# Main_board_schematic.net
KiCad netlist of a schematic drawn in EAGLE
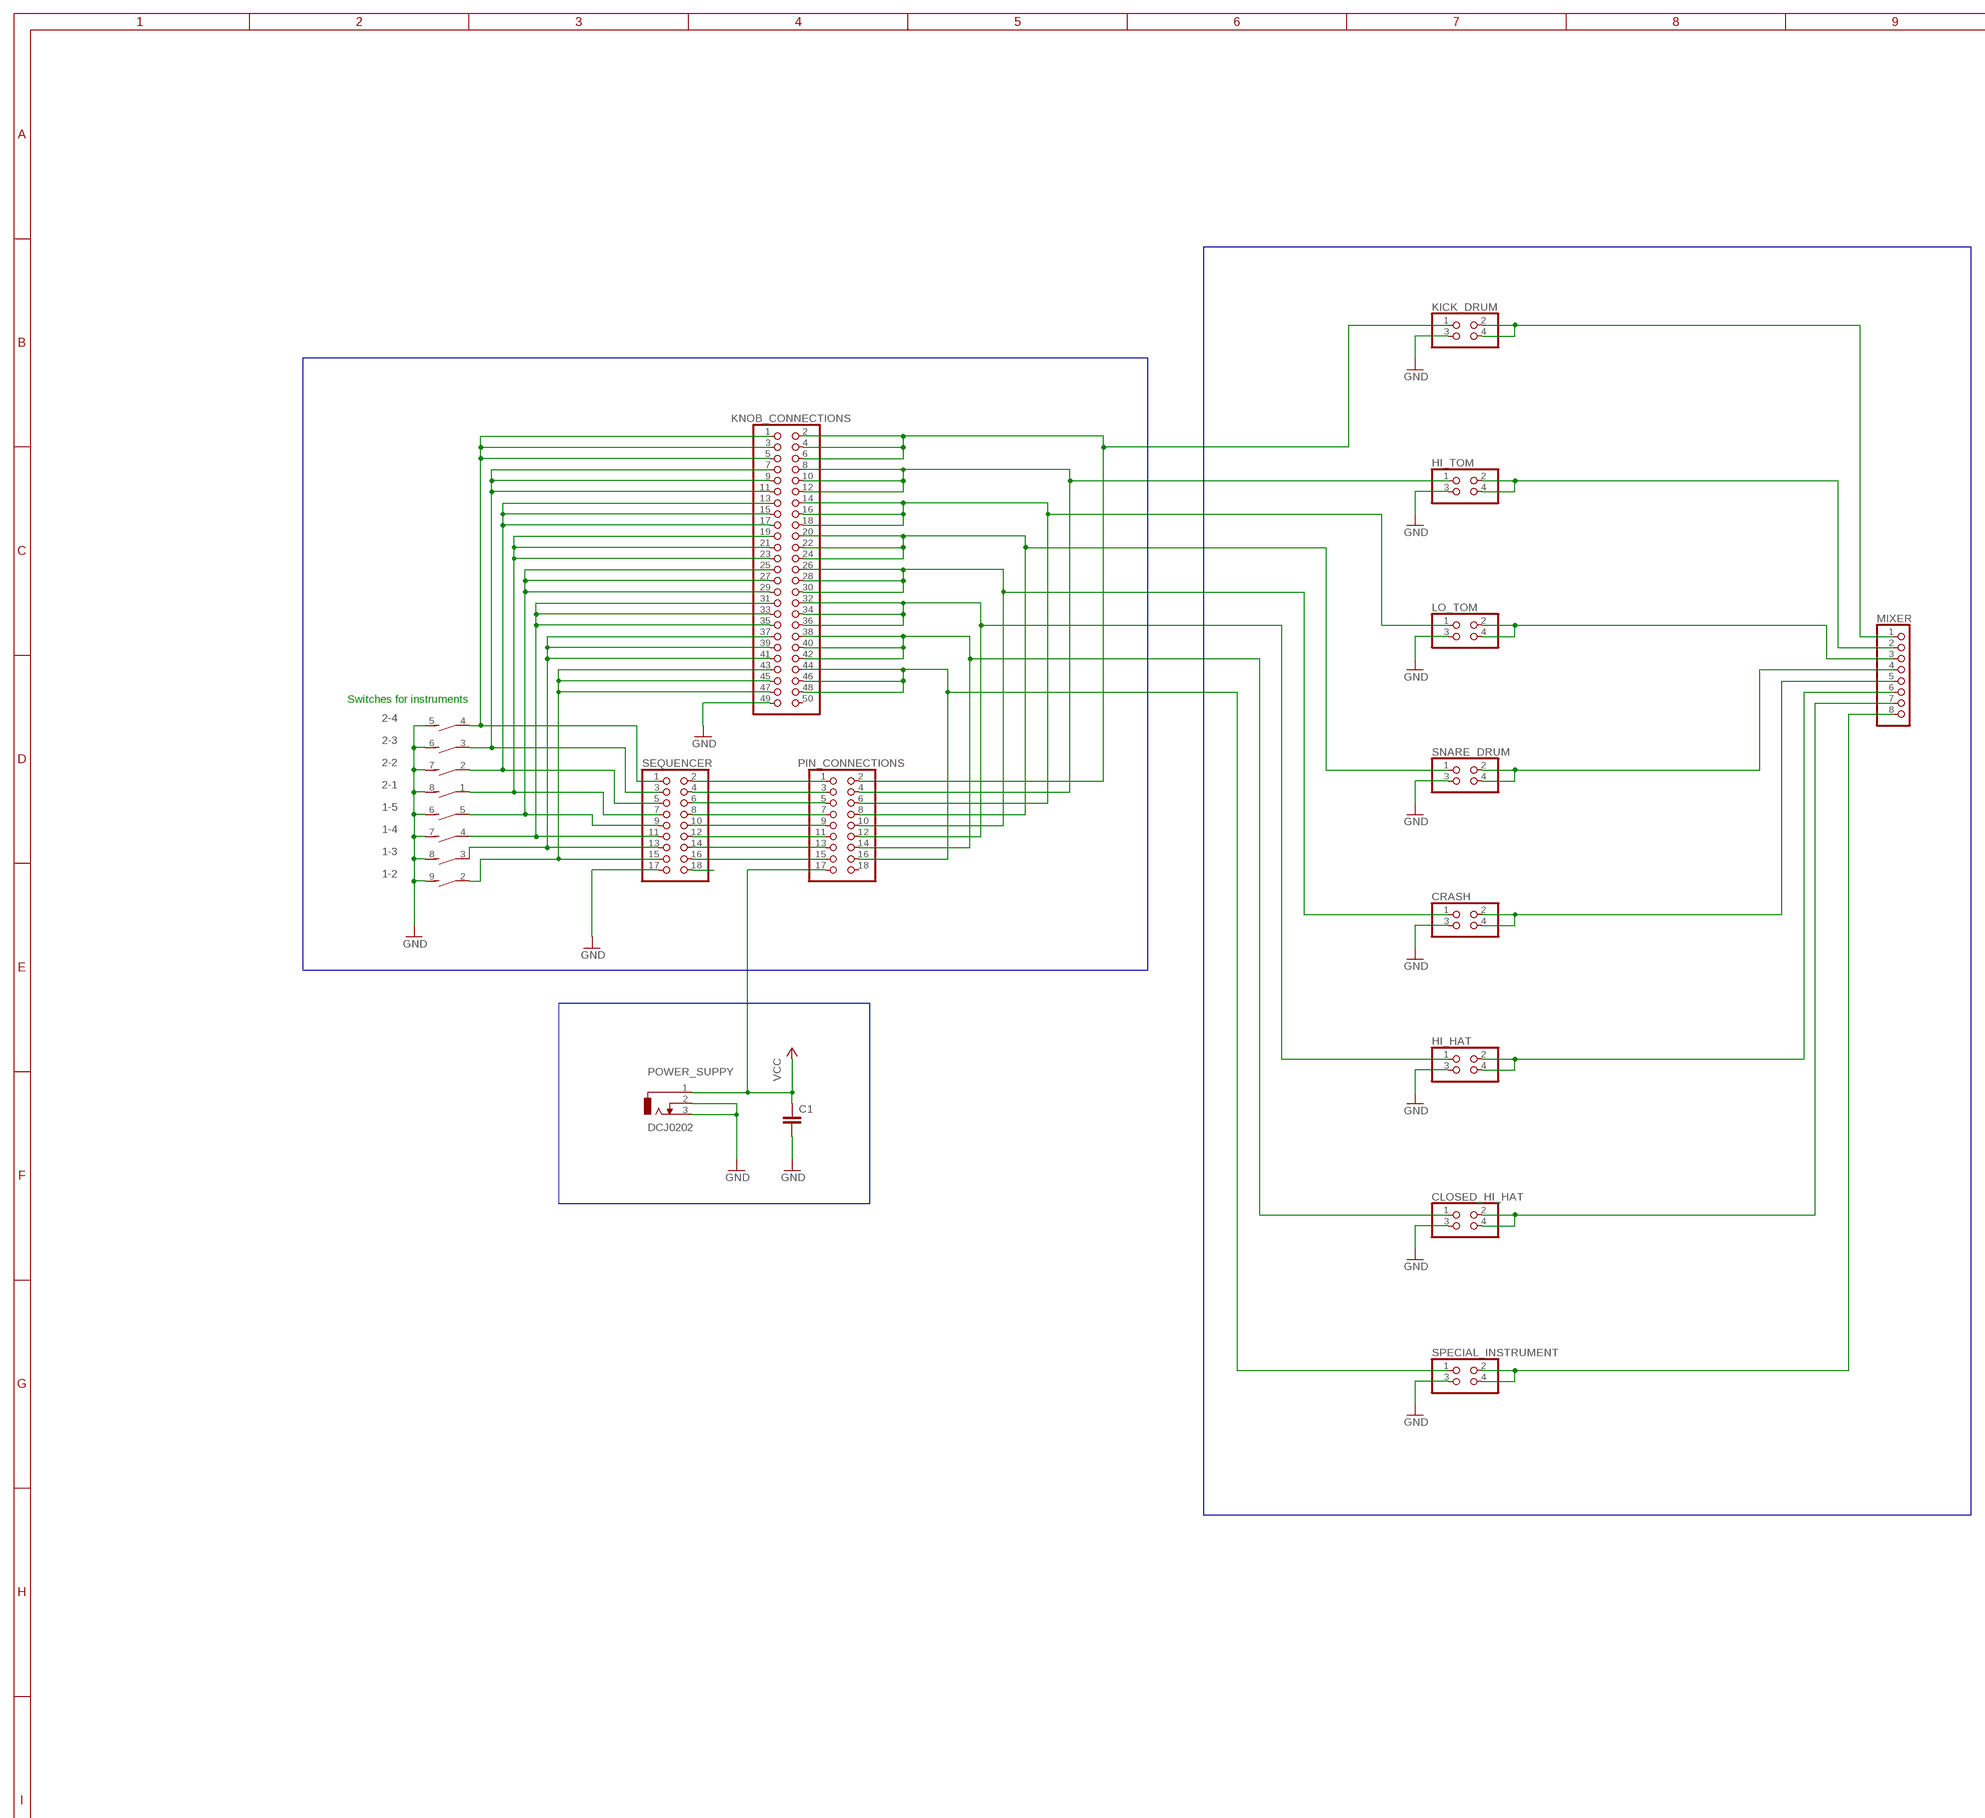
[diagram p0: schematic, sheet 1, part 1 of 2]
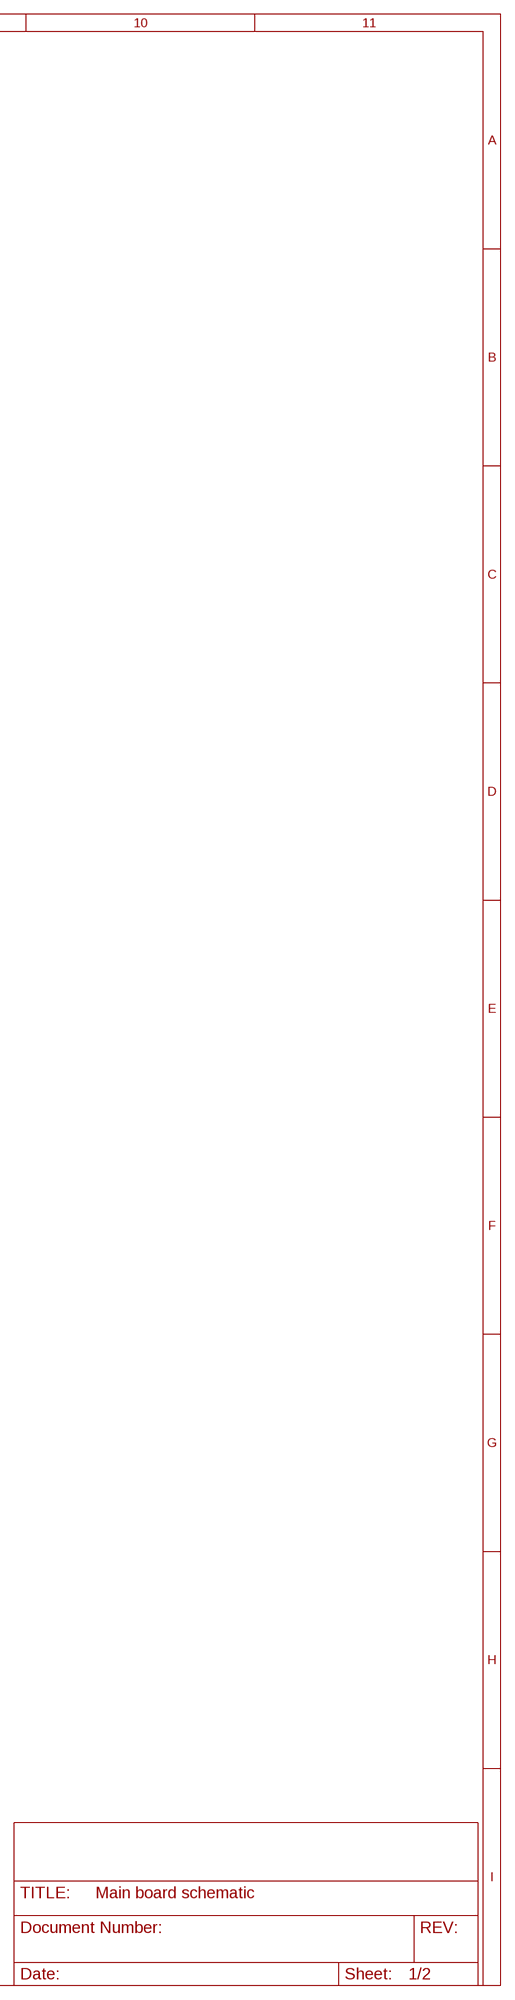
[diagram p1: schematic, sheet 1, part 2 of 2]
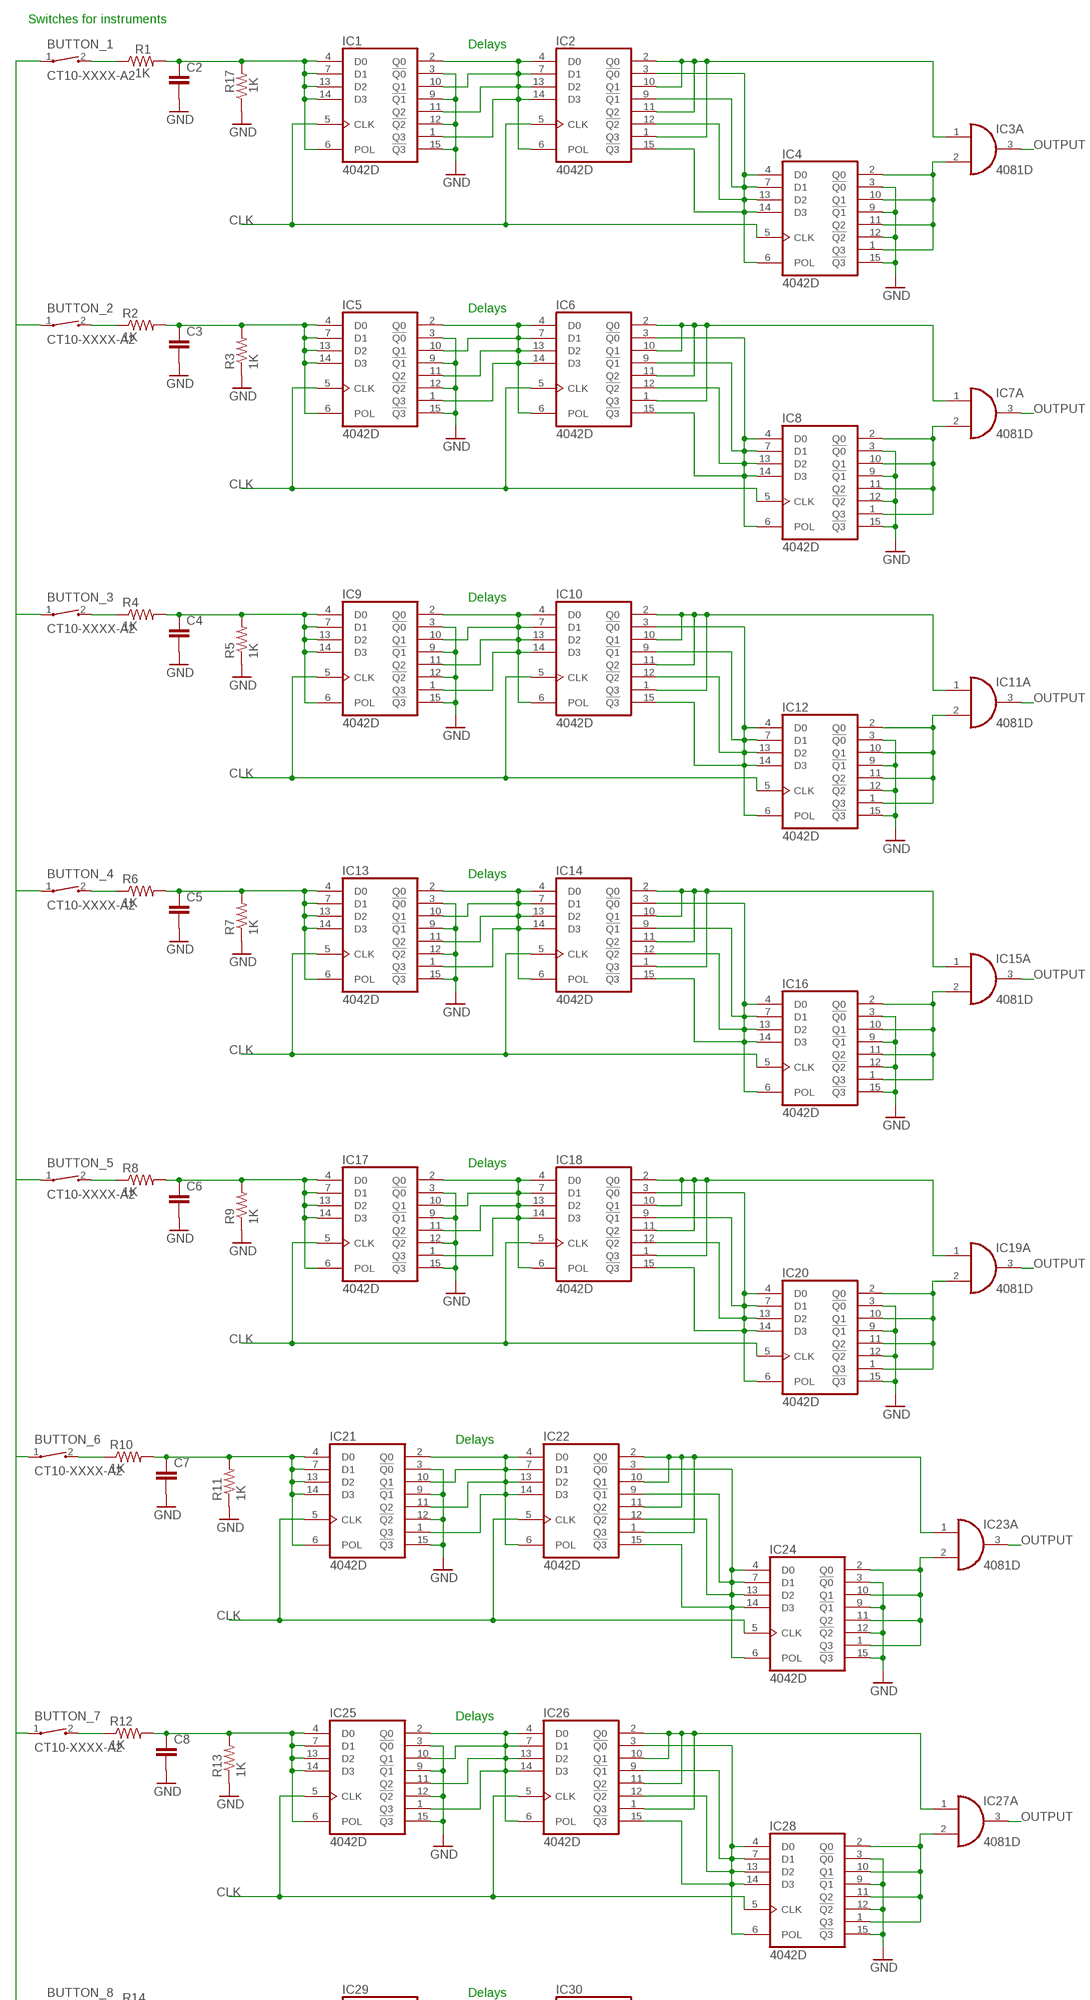
[diagram p2: schematic, sheet 2, part 1 of 3]
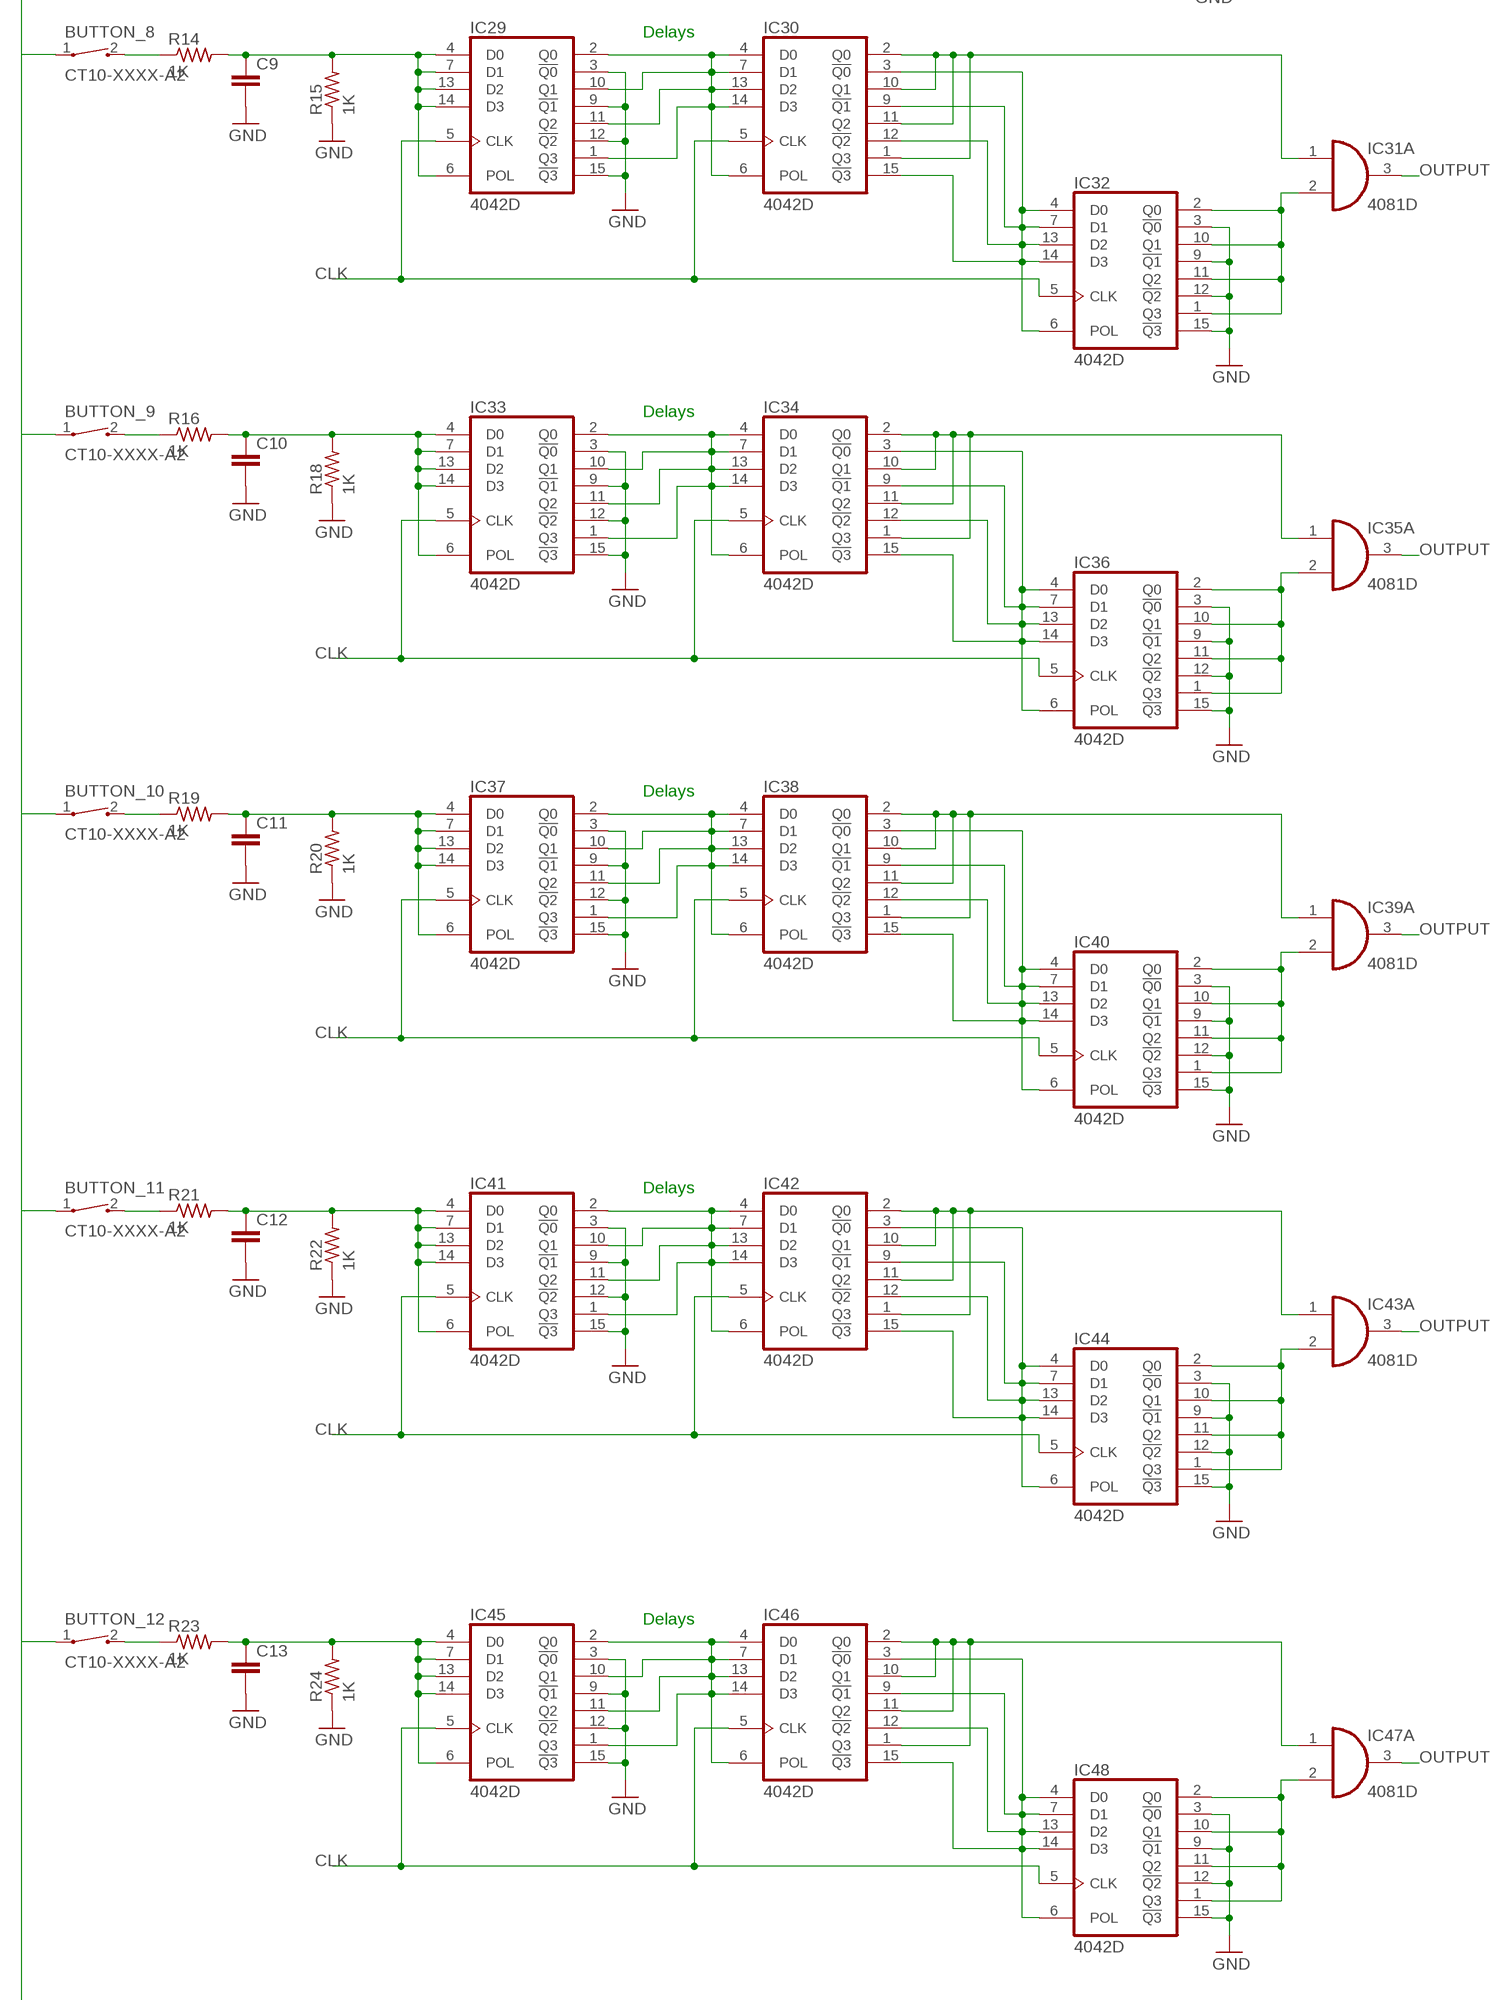
[diagram p3: schematic, sheet 2, part 2 of 3]
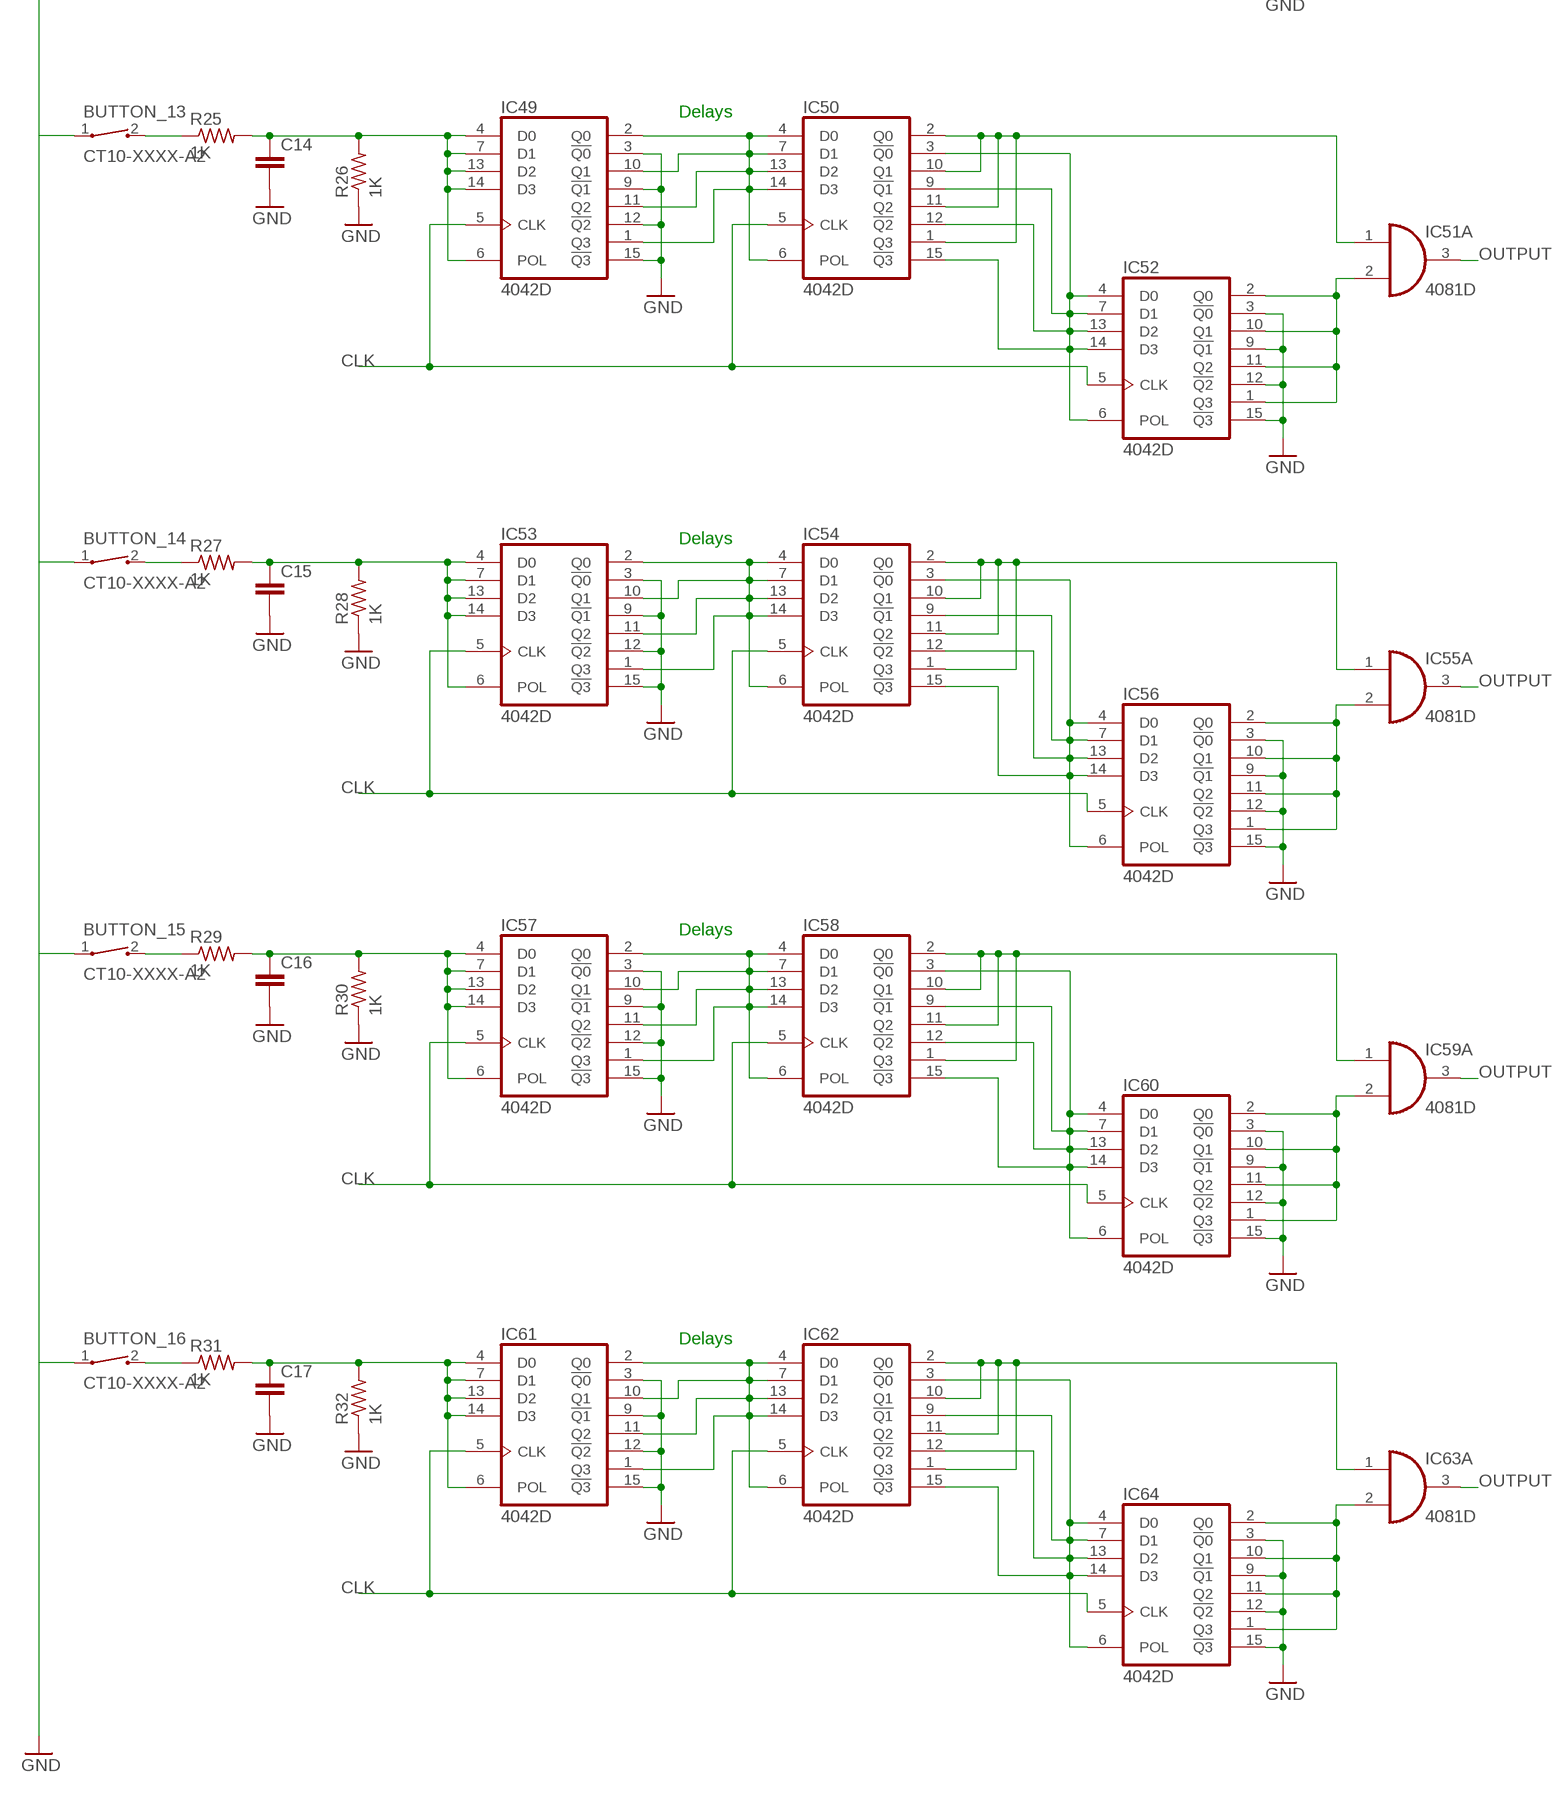
[diagram p4: schematic, sheet 2, part 3 of 3]

(export (version "E")
  (design (tool "Eeschema 10.0.6"))
  (components
    (comp (ref "BUTTON_1")
      (value "CT10-XXXX-A2")
      (footprint "eagle-import:CT10-XXXX-A2")
      (libsource (lib "eagle-import") (part "CT10-XXXX-A2"))
    )
    (comp (ref "BUTTON_2")
      (value "CT10-XXXX-A2")
      (footprint "eagle-import:CT10-XXXX-A2")
      (libsource (lib "eagle-import") (part "CT10-XXXX-A2"))
    )
    (comp (ref "BUTTON_3")
      (value "CT10-XXXX-A2")
      (footprint "eagle-import:CT10-XXXX-A2")
      (libsource (lib "eagle-import") (part "CT10-XXXX-A2"))
    )
    (comp (ref "BUTTON_4")
      (value "CT10-XXXX-A2")
      (footprint "eagle-import:CT10-XXXX-A2")
      (libsource (lib "eagle-import") (part "CT10-XXXX-A2"))
    )
    (comp (ref "BUTTON_5")
      (value "CT10-XXXX-A2")
      (footprint "eagle-import:CT10-XXXX-A2")
      (libsource (lib "eagle-import") (part "CT10-XXXX-A2"))
    )
    (comp (ref "BUTTON_6")
      (value "CT10-XXXX-A2")
      (footprint "eagle-import:CT10-XXXX-A2")
      (libsource (lib "eagle-import") (part "CT10-XXXX-A2"))
    )
    (comp (ref "BUTTON_7")
      (value "CT10-XXXX-A2")
      (footprint "eagle-import:CT10-XXXX-A2")
      (libsource (lib "eagle-import") (part "CT10-XXXX-A2"))
    )
    (comp (ref "BUTTON_8")
      (value "CT10-XXXX-A2")
      (footprint "eagle-import:CT10-XXXX-A2")
      (libsource (lib "eagle-import") (part "CT10-XXXX-A2"))
    )
    (comp (ref "BUTTON_9")
      (value "CT10-XXXX-A2")
      (footprint "eagle-import:CT10-XXXX-A2")
      (libsource (lib "eagle-import") (part "CT10-XXXX-A2"))
    )
    (comp (ref "BUTTON_10")
      (value "CT10-XXXX-A2")
      (footprint "eagle-import:CT10-XXXX-A2")
      (libsource (lib "eagle-import") (part "CT10-XXXX-A2"))
    )
    (comp (ref "BUTTON_11")
      (value "CT10-XXXX-A2")
      (footprint "eagle-import:CT10-XXXX-A2")
      (libsource (lib "eagle-import") (part "CT10-XXXX-A2"))
    )
    (comp (ref "BUTTON_12")
      (value "CT10-XXXX-A2")
      (footprint "eagle-import:CT10-XXXX-A2")
      (libsource (lib "eagle-import") (part "CT10-XXXX-A2"))
    )
    (comp (ref "BUTTON_13")
      (value "CT10-XXXX-A2")
      (footprint "eagle-import:CT10-XXXX-A2")
      (libsource (lib "eagle-import") (part "CT10-XXXX-A2"))
    )
    (comp (ref "BUTTON_14")
      (value "CT10-XXXX-A2")
      (footprint "eagle-import:CT10-XXXX-A2")
      (libsource (lib "eagle-import") (part "CT10-XXXX-A2"))
    )
    (comp (ref "BUTTON_15")
      (value "CT10-XXXX-A2")
      (footprint "eagle-import:CT10-XXXX-A2")
      (libsource (lib "eagle-import") (part "CT10-XXXX-A2"))
    )
    (comp (ref "BUTTON_16")
      (value "CT10-XXXX-A2")
      (footprint "eagle-import:CT10-XXXX-A2")
      (libsource (lib "eagle-import") (part "CT10-XXXX-A2"))
    )
    (comp (ref "C2")
      (value "C5/3")
      (footprint "eagle-import:C5B3")
      (libsource (lib "eagle-import") (part "C5/3"))
    )
    (comp (ref "C3")
      (value "C5/3")
      (footprint "eagle-import:C5B3")
      (libsource (lib "eagle-import") (part "C5/3"))
    )
    (comp (ref "C4")
      (value "C5/3")
      (footprint "eagle-import:C5B3")
      (libsource (lib "eagle-import") (part "C5/3"))
    )
    (comp (ref "C5")
      (value "C5/3")
      (footprint "eagle-import:C5B3")
      (libsource (lib "eagle-import") (part "C5/3"))
    )
    (comp (ref "C6")
      (value "C5/3")
      (footprint "eagle-import:C5B3")
      (libsource (lib "eagle-import") (part "C5/3"))
    )
    (comp (ref "C7")
      (value "C5/3")
      (footprint "eagle-import:C5B3")
      (libsource (lib "eagle-import") (part "C5/3"))
    )
    (comp (ref "C8")
      (value "C5/3")
      (footprint "eagle-import:C5B3")
      (libsource (lib "eagle-import") (part "C5/3"))
    )
    (comp (ref "C9")
      (value "C5/3")
      (footprint "eagle-import:C5B3")
      (libsource (lib "eagle-import") (part "C5/3"))
    )
    (comp (ref "C10")
      (value "C5/3")
      (footprint "eagle-import:C5B3")
      (libsource (lib "eagle-import") (part "C5/3"))
    )
    (comp (ref "C11")
      (value "C5/3")
      (footprint "eagle-import:C5B3")
      (libsource (lib "eagle-import") (part "C5/3"))
    )
    (comp (ref "C12")
      (value "C5/3")
      (footprint "eagle-import:C5B3")
      (libsource (lib "eagle-import") (part "C5/3"))
    )
    (comp (ref "C13")
      (value "C5/3")
      (footprint "eagle-import:C5B3")
      (libsource (lib "eagle-import") (part "C5/3"))
    )
    (comp (ref "C14")
      (value "C5/3")
      (footprint "eagle-import:C5B3")
      (libsource (lib "eagle-import") (part "C5/3"))
    )
    (comp (ref "C15")
      (value "C5/3")
      (footprint "eagle-import:C5B3")
      (libsource (lib "eagle-import") (part "C5/3"))
    )
    (comp (ref "C16")
      (value "C5/3")
      (footprint "eagle-import:C5B3")
      (libsource (lib "eagle-import") (part "C5/3"))
    )
    (comp (ref "C17")
      (value "C5/3")
      (footprint "eagle-import:C5B3")
      (libsource (lib "eagle-import") (part "C5/3"))
    )
    (comp (ref "IC1")
      (value "4042D")
      (footprint "eagle-import:SO16")
      (libsource (lib "eagle-import") (part "4042D"))
    )
    (comp (ref "IC2")
      (value "4042D")
      (footprint "eagle-import:SO16")
      (libsource (lib "eagle-import") (part "4042D"))
    )
    (comp (ref "IC3")
      (value "4081D")
      (footprint "eagle-import:SO14")
      (libsource (lib "eagle-import") (part "4081D"))
    )
    (comp (ref "IC4")
      (value "4042D")
      (footprint "eagle-import:SO16")
      (libsource (lib "eagle-import") (part "4042D"))
    )
    (comp (ref "IC5")
      (value "4042D")
      (footprint "eagle-import:SO16")
      (libsource (lib "eagle-import") (part "4042D"))
    )
    (comp (ref "IC6")
      (value "4042D")
      (footprint "eagle-import:SO16")
      (libsource (lib "eagle-import") (part "4042D"))
    )
    (comp (ref "IC7")
      (value "4081D")
      (footprint "eagle-import:SO14")
      (libsource (lib "eagle-import") (part "4081D"))
    )
    (comp (ref "IC8")
      (value "4042D")
      (footprint "eagle-import:SO16")
      (libsource (lib "eagle-import") (part "4042D"))
    )
    (comp (ref "IC9")
      (value "4042D")
      (footprint "eagle-import:SO16")
      (libsource (lib "eagle-import") (part "4042D"))
    )
    (comp (ref "IC10")
      (value "4042D")
      (footprint "eagle-import:SO16")
      (libsource (lib "eagle-import") (part "4042D"))
    )
    (comp (ref "IC11")
      (value "4081D")
      (footprint "eagle-import:SO14")
      (libsource (lib "eagle-import") (part "4081D"))
    )
    (comp (ref "IC12")
      (value "4042D")
      (footprint "eagle-import:SO16")
      (libsource (lib "eagle-import") (part "4042D"))
    )
    (comp (ref "IC13")
      (value "4042D")
      (footprint "eagle-import:SO16")
      (libsource (lib "eagle-import") (part "4042D"))
    )
    (comp (ref "IC14")
      (value "4042D")
      (footprint "eagle-import:SO16")
      (libsource (lib "eagle-import") (part "4042D"))
    )
    (comp (ref "IC15")
      (value "4081D")
      (footprint "eagle-import:SO14")
      (libsource (lib "eagle-import") (part "4081D"))
    )
    (comp (ref "IC16")
      (value "4042D")
      (footprint "eagle-import:SO16")
      (libsource (lib "eagle-import") (part "4042D"))
    )
    (comp (ref "IC17")
      (value "4042D")
      (footprint "eagle-import:SO16")
      (libsource (lib "eagle-import") (part "4042D"))
    )
    (comp (ref "IC18")
      (value "4042D")
      (footprint "eagle-import:SO16")
      (libsource (lib "eagle-import") (part "4042D"))
    )
    (comp (ref "IC19")
      (value "4081D")
      (footprint "eagle-import:SO14")
      (libsource (lib "eagle-import") (part "4081D"))
    )
    (comp (ref "IC20")
      (value "4042D")
      (footprint "eagle-import:SO16")
      (libsource (lib "eagle-import") (part "4042D"))
    )
    (comp (ref "IC21")
      (value "4042D")
      (footprint "eagle-import:SO16")
      (libsource (lib "eagle-import") (part "4042D"))
    )
    (comp (ref "IC22")
      (value "4042D")
      (footprint "eagle-import:SO16")
      (libsource (lib "eagle-import") (part "4042D"))
    )
    (comp (ref "IC23")
      (value "4081D")
      (footprint "eagle-import:SO14")
      (libsource (lib "eagle-import") (part "4081D"))
    )
    (comp (ref "IC24")
      (value "4042D")
      (footprint "eagle-import:SO16")
      (libsource (lib "eagle-import") (part "4042D"))
    )
    (comp (ref "IC25")
      (value "4042D")
      (footprint "eagle-import:SO16")
      (libsource (lib "eagle-import") (part "4042D"))
    )
    (comp (ref "IC26")
      (value "4042D")
      (footprint "eagle-import:SO16")
      (libsource (lib "eagle-import") (part "4042D"))
    )
    (comp (ref "IC27")
      (value "4081D")
      (footprint "eagle-import:SO14")
      (libsource (lib "eagle-import") (part "4081D"))
    )
    (comp (ref "IC28")
      (value "4042D")
      (footprint "eagle-import:SO16")
      (libsource (lib "eagle-import") (part "4042D"))
    )
    (comp (ref "IC29")
      (value "4042D")
      (footprint "eagle-import:SO16")
      (libsource (lib "eagle-import") (part "4042D"))
    )
    (comp (ref "IC30")
      (value "4042D")
      (footprint "eagle-import:SO16")
      (libsource (lib "eagle-import") (part "4042D"))
    )
    (comp (ref "IC31")
      (value "4081D")
      (footprint "eagle-import:SO14")
      (libsource (lib "eagle-import") (part "4081D"))
    )
    (comp (ref "IC32")
      (value "4042D")
      (footprint "eagle-import:SO16")
      (libsource (lib "eagle-import") (part "4042D"))
    )
    (comp (ref "IC33")
      (value "4042D")
      (footprint "eagle-import:SO16")
      (libsource (lib "eagle-import") (part "4042D"))
    )
    (comp (ref "IC34")
      (value "4042D")
      (footprint "eagle-import:SO16")
      (libsource (lib "eagle-import") (part "4042D"))
    )
    (comp (ref "IC35")
      (value "4081D")
      (footprint "eagle-import:SO14")
      (libsource (lib "eagle-import") (part "4081D"))
    )
    (comp (ref "IC36")
      (value "4042D")
      (footprint "eagle-import:SO16")
      (libsource (lib "eagle-import") (part "4042D"))
    )
    (comp (ref "IC37")
      (value "4042D")
      (footprint "eagle-import:SO16")
      (libsource (lib "eagle-import") (part "4042D"))
    )
    (comp (ref "IC38")
      (value "4042D")
      (footprint "eagle-import:SO16")
      (libsource (lib "eagle-import") (part "4042D"))
    )
    (comp (ref "IC39")
      (value "4081D")
      (footprint "eagle-import:SO14")
      (libsource (lib "eagle-import") (part "4081D"))
    )
    (comp (ref "IC40")
      (value "4042D")
      (footprint "eagle-import:SO16")
      (libsource (lib "eagle-import") (part "4042D"))
    )
    (comp (ref "IC41")
      (value "4042D")
      (footprint "eagle-import:SO16")
      (libsource (lib "eagle-import") (part "4042D"))
    )
    (comp (ref "IC42")
      (value "4042D")
      (footprint "eagle-import:SO16")
      (libsource (lib "eagle-import") (part "4042D"))
    )
    (comp (ref "IC43")
      (value "4081D")
      (footprint "eagle-import:SO14")
      (libsource (lib "eagle-import") (part "4081D"))
    )
    (comp (ref "IC44")
      (value "4042D")
      (footprint "eagle-import:SO16")
      (libsource (lib "eagle-import") (part "4042D"))
    )
    (comp (ref "IC45")
      (value "4042D")
      (footprint "eagle-import:SO16")
      (libsource (lib "eagle-import") (part "4042D"))
    )
    (comp (ref "IC46")
      (value "4042D")
      (footprint "eagle-import:SO16")
      (libsource (lib "eagle-import") (part "4042D"))
    )
    (comp (ref "IC47")
      (value "4081D")
      (footprint "eagle-import:SO14")
      (libsource (lib "eagle-import") (part "4081D"))
    )
    (comp (ref "IC48")
      (value "4042D")
      (footprint "eagle-import:SO16")
      (libsource (lib "eagle-import") (part "4042D"))
    )
    (comp (ref "IC49")
      (value "4042D")
      (footprint "eagle-import:SO16")
      (libsource (lib "eagle-import") (part "4042D"))
    )
    (comp (ref "IC50")
      (value "4042D")
      (footprint "eagle-import:SO16")
      (libsource (lib "eagle-import") (part "4042D"))
    )
    (comp (ref "IC51")
      (value "4081D")
      (footprint "eagle-import:SO14")
      (libsource (lib "eagle-import") (part "4081D"))
    )
    (comp (ref "IC52")
      (value "4042D")
      (footprint "eagle-import:SO16")
      (libsource (lib "eagle-import") (part "4042D"))
    )
    (comp (ref "IC53")
      (value "4042D")
      (footprint "eagle-import:SO16")
      (libsource (lib "eagle-import") (part "4042D"))
    )
    (comp (ref "IC54")
      (value "4042D")
      (footprint "eagle-import:SO16")
      (libsource (lib "eagle-import") (part "4042D"))
    )
    (comp (ref "IC55")
      (value "4081D")
      (footprint "eagle-import:SO14")
      (libsource (lib "eagle-import") (part "4081D"))
    )
    (comp (ref "IC56")
      (value "4042D")
      (footprint "eagle-import:SO16")
      (libsource (lib "eagle-import") (part "4042D"))
    )
    (comp (ref "IC57")
      (value "4042D")
      (footprint "eagle-import:SO16")
      (libsource (lib "eagle-import") (part "4042D"))
    )
    (comp (ref "IC58")
      (value "4042D")
      (footprint "eagle-import:SO16")
      (libsource (lib "eagle-import") (part "4042D"))
    )
    (comp (ref "IC59")
      (value "4081D")
      (footprint "eagle-import:SO14")
      (libsource (lib "eagle-import") (part "4081D"))
    )
    (comp (ref "IC60")
      (value "4042D")
      (footprint "eagle-import:SO16")
      (libsource (lib "eagle-import") (part "4042D"))
    )
    (comp (ref "IC61")
      (value "4042D")
      (footprint "eagle-import:SO16")
      (libsource (lib "eagle-import") (part "4042D"))
    )
    (comp (ref "IC62")
      (value "4042D")
      (footprint "eagle-import:SO16")
      (libsource (lib "eagle-import") (part "4042D"))
    )
    (comp (ref "IC63")
      (value "4081D")
      (footprint "eagle-import:SO14")
      (libsource (lib "eagle-import") (part "4081D"))
    )
    (comp (ref "IC64")
      (value "4042D")
      (footprint "eagle-import:SO16")
      (libsource (lib "eagle-import") (part "4042D"))
    )
    (comp (ref "R1")
      (value "1K")
      (footprint "eagle-import:0204_7")
      (libsource (lib "eagle-import") (part "R-US_0204/7"))
    )
    (comp (ref "R2")
      (value "1K")
      (footprint "eagle-import:0204_7")
      (libsource (lib "eagle-import") (part "R-US_0204/7"))
    )
    (comp (ref "R3")
      (value "1K")
      (footprint "eagle-import:0204_7")
      (libsource (lib "eagle-import") (part "R-US_0204/7"))
    )
    (comp (ref "R4")
      (value "1K")
      (footprint "eagle-import:0204_7")
      (libsource (lib "eagle-import") (part "R-US_0204/7"))
    )
    (comp (ref "R5")
      (value "1K")
      (footprint "eagle-import:0204_7")
      (libsource (lib "eagle-import") (part "R-US_0204/7"))
    )
    (comp (ref "R6")
      (value "1K")
      (footprint "eagle-import:0204_7")
      (libsource (lib "eagle-import") (part "R-US_0204/7"))
    )
    (comp (ref "R7")
      (value "1K")
      (footprint "eagle-import:0204_7")
      (libsource (lib "eagle-import") (part "R-US_0204/7"))
    )
    (comp (ref "R8")
      (value "1K")
      (footprint "eagle-import:0204_7")
      (libsource (lib "eagle-import") (part "R-US_0204/7"))
    )
    (comp (ref "R9")
      (value "1K")
      (footprint "eagle-import:0204_7")
      (libsource (lib "eagle-import") (part "R-US_0204/7"))
    )
    (comp (ref "R10")
      (value "1K")
      (footprint "eagle-import:0204_7")
      (libsource (lib "eagle-import") (part "R-US_0204/7"))
    )
    (comp (ref "R11")
      (value "1K")
      (footprint "eagle-import:0204_7")
      (libsource (lib "eagle-import") (part "R-US_0204/7"))
    )
    (comp (ref "R12")
      (value "1K")
      (footprint "eagle-import:0204_7")
      (libsource (lib "eagle-import") (part "R-US_0204/7"))
    )
    (comp (ref "R13")
      (value "1K")
      (footprint "eagle-import:0204_7")
      (libsource (lib "eagle-import") (part "R-US_0204/7"))
    )
    (comp (ref "R14")
      (value "1K")
      (footprint "eagle-import:0204_7")
      (libsource (lib "eagle-import") (part "R-US_0204/7"))
    )
    (comp (ref "R15")
      (value "1K")
      (footprint "eagle-import:0204_7")
      (libsource (lib "eagle-import") (part "R-US_0204/7"))
    )
    (comp (ref "R16")
      (value "1K")
      (footprint "eagle-import:0204_7")
      (libsource (lib "eagle-import") (part "R-US_0204/7"))
    )
    (comp (ref "R17")
      (value "1K")
      (footprint "eagle-import:0204_7")
      (libsource (lib "eagle-import") (part "R-US_0204/7"))
    )
    (comp (ref "R18")
      (value "1K")
      (footprint "eagle-import:0204_7")
      (libsource (lib "eagle-import") (part "R-US_0204/7"))
    )
    (comp (ref "R19")
      (value "1K")
      (footprint "eagle-import:0204_7")
      (libsource (lib "eagle-import") (part "R-US_0204/7"))
    )
    (comp (ref "R20")
      (value "1K")
      (footprint "eagle-import:0204_7")
      (libsource (lib "eagle-import") (part "R-US_0204/7"))
    )
    (comp (ref "R21")
      (value "1K")
      (footprint "eagle-import:0204_7")
      (libsource (lib "eagle-import") (part "R-US_0204/7"))
    )
    (comp (ref "R22")
      (value "1K")
      (footprint "eagle-import:0204_7")
      (libsource (lib "eagle-import") (part "R-US_0204/7"))
    )
    (comp (ref "R23")
      (value "1K")
      (footprint "eagle-import:0204_7")
      (libsource (lib "eagle-import") (part "R-US_0204/7"))
    )
    (comp (ref "R24")
      (value "1K")
      (footprint "eagle-import:0204_7")
      (libsource (lib "eagle-import") (part "R-US_0204/7"))
    )
    (comp (ref "R25")
      (value "1K")
      (footprint "eagle-import:0204_7")
      (libsource (lib "eagle-import") (part "R-US_0204/7"))
    )
    (comp (ref "R26")
      (value "1K")
      (footprint "eagle-import:0204_7")
      (libsource (lib "eagle-import") (part "R-US_0204/7"))
    )
    (comp (ref "R27")
      (value "1K")
      (footprint "eagle-import:0204_7")
      (libsource (lib "eagle-import") (part "R-US_0204/7"))
    )
    (comp (ref "R28")
      (value "1K")
      (footprint "eagle-import:0204_7")
      (libsource (lib "eagle-import") (part "R-US_0204/7"))
    )
    (comp (ref "R29")
      (value "1K")
      (footprint "eagle-import:0204_7")
      (libsource (lib "eagle-import") (part "R-US_0204/7"))
    )
    (comp (ref "R30")
      (value "1K")
      (footprint "eagle-import:0204_7")
      (libsource (lib "eagle-import") (part "R-US_0204/7"))
    )
    (comp (ref "R31")
      (value "1K")
      (footprint "eagle-import:0204_7")
      (libsource (lib "eagle-import") (part "R-US_0204/7"))
    )
    (comp (ref "R32")
      (value "1K")
      (footprint "eagle-import:0204_7")
      (libsource (lib "eagle-import") (part "R-US_0204/7"))
    )
    (comp (ref "1")
      (value "DS05E")
      (footprint "eagle-import:DS-05")
      (libsource (lib "eagle-import") (part "DS05E"))
    )
    (comp (ref "2")
      (value "DIP04S")
      (footprint "eagle-import:DIP04S")
      (libsource (lib "eagle-import") (part "DIP04S"))
    )
    (comp (ref "C1")
      (value "C2,5-3")
      (footprint "eagle-import:C2.5-3")
      (libsource (lib "eagle-import") (part "C2,5-3"))
    )
    (comp (ref "CLOSED_HI_HAT")
      (value "PINHD-2X2")
      (footprint "eagle-import:2X02")
      (libsource (lib "eagle-import") (part "PINHD-2X2"))
    )
    (comp (ref "CRASH")
      (value "PINHD-2X2")
      (footprint "eagle-import:2X02")
      (libsource (lib "eagle-import") (part "PINHD-2X2"))
    )
    (comp (ref "HI_HAT")
      (value "PINHD-2X2")
      (footprint "eagle-import:2X02")
      (libsource (lib "eagle-import") (part "PINHD-2X2"))
    )
    (comp (ref "HI_TOM")
      (value "PINHD-2X2")
      (footprint "eagle-import:2X02")
      (libsource (lib "eagle-import") (part "PINHD-2X2"))
    )
    (comp (ref "KICK_DRUM")
      (value "PINHD-2X2")
      (footprint "eagle-import:2X02")
      (libsource (lib "eagle-import") (part "PINHD-2X2"))
    )
    (comp (ref "KNOB_CONNECTIONS")
      (value "PINHD-2X25")
      (footprint "eagle-import:2X25")
      (libsource (lib "eagle-import") (part "PINHD-2X25"))
    )
    (comp (ref "LO_TOM")
      (value "PINHD-2X2")
      (footprint "eagle-import:2X02")
      (libsource (lib "eagle-import") (part "PINHD-2X2"))
    )
    (comp (ref "MIXER")
      (value "PINHD-1X8")
      (footprint "eagle-import:1X08")
      (libsource (lib "eagle-import") (part "PINHD-1X8"))
    )
    (comp (ref "PIN_CONNECTIONS")
      (value "PINHD-2X9")
      (footprint "eagle-import:2X09")
      (libsource (lib "eagle-import") (part "PINHD-2X9"))
    )
    (comp (ref "POWER_SUPPY")
      (value "DCJ0202")
      (footprint "eagle-import:DCJ0202")
      (libsource (lib "eagle-import") (part "DCJ0202"))
    )
    (comp (ref "SEQUENCER")
      (value "PINHD-2X9")
      (footprint "eagle-import:2X09")
      (libsource (lib "eagle-import") (part "PINHD-2X9"))
    )
    (comp (ref "SNARE_DRUM")
      (value "PINHD-2X2")
      (footprint "eagle-import:2X02")
      (libsource (lib "eagle-import") (part "PINHD-2X2"))
    )
    (comp (ref "SPECIAL_INSTRUMENT")
      (value "PINHD-2X2")
      (footprint "eagle-import:2X02")
      (libsource (lib "eagle-import") (part "PINHD-2X2"))
    )
  )
  (nets
    (net (code "1") (name "CLK") (class "Default")
      (node (ref "IC1") (pin "5") (pinfunction "CLK_5") (pintype "input"))
      (node (ref "IC10") (pin "5") (pinfunction "CLK_5") (pintype "input"))
      (node (ref "IC12") (pin "5") (pinfunction "CLK_5") (pintype "input"))
      (node (ref "IC13") (pin "5") (pinfunction "CLK_5") (pintype "input"))
      (node (ref "IC14") (pin "5") (pinfunction "CLK_5") (pintype "input"))
      (node (ref "IC16") (pin "5") (pinfunction "CLK_5") (pintype "input"))
      (node (ref "IC17") (pin "5") (pinfunction "CLK_5") (pintype "input"))
      (node (ref "IC18") (pin "5") (pinfunction "CLK_5") (pintype "input"))
      (node (ref "IC2") (pin "5") (pinfunction "CLK_5") (pintype "input"))
      (node (ref "IC20") (pin "5") (pinfunction "CLK_5") (pintype "input"))
      (node (ref "IC21") (pin "5") (pinfunction "CLK_5") (pintype "input"))
      (node (ref "IC22") (pin "5") (pinfunction "CLK_5") (pintype "input"))
      (node (ref "IC24") (pin "5") (pinfunction "CLK_5") (pintype "input"))
      (node (ref "IC25") (pin "5") (pinfunction "CLK_5") (pintype "input"))
      (node (ref "IC26") (pin "5") (pinfunction "CLK_5") (pintype "input"))
      (node (ref "IC28") (pin "5") (pinfunction "CLK_5") (pintype "input"))
      (node (ref "IC29") (pin "5") (pinfunction "CLK_5") (pintype "input"))
      (node (ref "IC30") (pin "5") (pinfunction "CLK_5") (pintype "input"))
      (node (ref "IC32") (pin "5") (pinfunction "CLK_5") (pintype "input"))
      (node (ref "IC33") (pin "5") (pinfunction "CLK_5") (pintype "input"))
      (node (ref "IC34") (pin "5") (pinfunction "CLK_5") (pintype "input"))
      (node (ref "IC36") (pin "5") (pinfunction "CLK_5") (pintype "input"))
      (node (ref "IC37") (pin "5") (pinfunction "CLK_5") (pintype "input"))
      (node (ref "IC38") (pin "5") (pinfunction "CLK_5") (pintype "input"))
      (node (ref "IC4") (pin "5") (pinfunction "CLK_5") (pintype "input"))
      (node (ref "IC40") (pin "5") (pinfunction "CLK_5") (pintype "input"))
      (node (ref "IC41") (pin "5") (pinfunction "CLK_5") (pintype "input"))
      (node (ref "IC42") (pin "5") (pinfunction "CLK_5") (pintype "input"))
      (node (ref "IC44") (pin "5") (pinfunction "CLK_5") (pintype "input"))
      (node (ref "IC45") (pin "5") (pinfunction "CLK_5") (pintype "input"))
      (node (ref "IC46") (pin "5") (pinfunction "CLK_5") (pintype "input"))
      (node (ref "IC48") (pin "5") (pinfunction "CLK_5") (pintype "input"))
      (node (ref "IC49") (pin "5") (pinfunction "CLK_5") (pintype "input"))
      (node (ref "IC5") (pin "5") (pinfunction "CLK_5") (pintype "input"))
      (node (ref "IC50") (pin "5") (pinfunction "CLK_5") (pintype "input"))
      (node (ref "IC52") (pin "5") (pinfunction "CLK_5") (pintype "input"))
      (node (ref "IC53") (pin "5") (pinfunction "CLK_5") (pintype "input"))
      (node (ref "IC54") (pin "5") (pinfunction "CLK_5") (pintype "input"))
      (node (ref "IC56") (pin "5") (pinfunction "CLK_5") (pintype "input"))
      (node (ref "IC57") (pin "5") (pinfunction "CLK_5") (pintype "input"))
      (node (ref "IC58") (pin "5") (pinfunction "CLK_5") (pintype "input"))
      (node (ref "IC6") (pin "5") (pinfunction "CLK_5") (pintype "input"))
      (node (ref "IC60") (pin "5") (pinfunction "CLK_5") (pintype "input"))
      (node (ref "IC61") (pin "5") (pinfunction "CLK_5") (pintype "input"))
      (node (ref "IC62") (pin "5") (pinfunction "CLK_5") (pintype "input"))
      (node (ref "IC64") (pin "5") (pinfunction "CLK_5") (pintype "input"))
      (node (ref "IC8") (pin "5") (pinfunction "CLK_5") (pintype "input"))
      (node (ref "IC9") (pin "5") (pinfunction "CLK_5") (pintype "input"))
    )
    (net (code "2") (name "GND") (class "Default")
      (node (ref "1") (pin "6") (pinfunction "2_6") (pintype "passive"))
      (node (ref "1") (pin "7") (pinfunction "2_7") (pintype "passive"))
      (node (ref "1") (pin "8") (pinfunction "2_8") (pintype "passive"))
      (node (ref "1") (pin "9") (pinfunction "2_9") (pintype "passive"))
      (node (ref "2") (pin "5") (pinfunction "2_5") (pintype "passive"))
      (node (ref "2") (pin "6") (pinfunction "2_6") (pintype "passive"))
      (node (ref "2") (pin "7") (pinfunction "2_7") (pintype "passive"))
      (node (ref "2") (pin "8") (pinfunction "2_8") (pintype "passive"))
      (node (ref "BUTTON_1") (pin "1") (pinfunction "1_1") (pintype "passive"))
      (node (ref "C1") (pin "2") (pinfunction "2_2") (pintype "passive"))
      (node (ref "C10") (pin "2") (pinfunction "2_2") (pintype "passive"))
      (node (ref "C11") (pin "2") (pinfunction "2_2") (pintype "passive"))
      (node (ref "C12") (pin "2") (pinfunction "2_2") (pintype "passive"))
      (node (ref "C13") (pin "2") (pinfunction "2_2") (pintype "passive"))
      (node (ref "C14") (pin "2") (pinfunction "2_2") (pintype "passive"))
      (node (ref "C15") (pin "2") (pinfunction "2_2") (pintype "passive"))
      (node (ref "C16") (pin "2") (pinfunction "2_2") (pintype "passive"))
      (node (ref "C17") (pin "2") (pinfunction "2_2") (pintype "passive"))
      (node (ref "C2") (pin "2") (pinfunction "2_2") (pintype "passive"))
      (node (ref "C3") (pin "2") (pinfunction "2_2") (pintype "passive"))
      (node (ref "C4") (pin "2") (pinfunction "2_2") (pintype "passive"))
      (node (ref "C5") (pin "2") (pinfunction "2_2") (pintype "passive"))
      (node (ref "C6") (pin "2") (pinfunction "2_2") (pintype "passive"))
      (node (ref "C7") (pin "2") (pinfunction "2_2") (pintype "passive"))
      (node (ref "C8") (pin "2") (pinfunction "2_2") (pintype "passive"))
      (node (ref "C9") (pin "2") (pinfunction "2_2") (pintype "passive"))
      (node (ref "CLOSED_HI_HAT") (pin "3") (pinfunction "3_3") (pintype "passive"))
      (node (ref "CRASH") (pin "3") (pinfunction "3_3") (pintype "passive"))
      (node (ref "HI_HAT") (pin "3") (pinfunction "3_3") (pintype "passive"))
      (node (ref "HI_TOM") (pin "3") (pinfunction "3_3") (pintype "passive"))
      (node (ref "IC1") (pin "12") (pinfunction "~{Q2}_12") (pintype "output"))
      (node (ref "IC1") (pin "15") (pinfunction "~{Q3}_15") (pintype "output"))
      (node (ref "IC1") (pin "3") (pinfunction "~{Q0}_3") (pintype "output"))
      (node (ref "IC1") (pin "9") (pinfunction "~{Q1}_9") (pintype "output"))
      (node (ref "IC12") (pin "12") (pinfunction "~{Q2}_12") (pintype "output"))
      (node (ref "IC12") (pin "15") (pinfunction "~{Q3}_15") (pintype "output"))
      (node (ref "IC12") (pin "3") (pinfunction "~{Q0}_3") (pintype "output"))
      (node (ref "IC12") (pin "9") (pinfunction "~{Q1}_9") (pintype "output"))
      (node (ref "IC13") (pin "12") (pinfunction "~{Q2}_12") (pintype "output"))
      (node (ref "IC13") (pin "15") (pinfunction "~{Q3}_15") (pintype "output"))
      (node (ref "IC13") (pin "3") (pinfunction "~{Q0}_3") (pintype "output"))
      (node (ref "IC13") (pin "9") (pinfunction "~{Q1}_9") (pintype "output"))
      (node (ref "IC16") (pin "12") (pinfunction "~{Q2}_12") (pintype "output"))
      (node (ref "IC16") (pin "15") (pinfunction "~{Q3}_15") (pintype "output"))
      (node (ref "IC16") (pin "3") (pinfunction "~{Q0}_3") (pintype "output"))
      (node (ref "IC16") (pin "9") (pinfunction "~{Q1}_9") (pintype "output"))
      (node (ref "IC17") (pin "12") (pinfunction "~{Q2}_12") (pintype "output"))
      (node (ref "IC17") (pin "15") (pinfunction "~{Q3}_15") (pintype "output"))
      (node (ref "IC17") (pin "3") (pinfunction "~{Q0}_3") (pintype "output"))
      (node (ref "IC17") (pin "9") (pinfunction "~{Q1}_9") (pintype "output"))
      (node (ref "IC20") (pin "12") (pinfunction "~{Q2}_12") (pintype "output"))
      (node (ref "IC20") (pin "15") (pinfunction "~{Q3}_15") (pintype "output"))
      (node (ref "IC20") (pin "3") (pinfunction "~{Q0}_3") (pintype "output"))
      (node (ref "IC20") (pin "9") (pinfunction "~{Q1}_9") (pintype "output"))
      (node (ref "IC21") (pin "12") (pinfunction "~{Q2}_12") (pintype "output"))
      (node (ref "IC21") (pin "15") (pinfunction "~{Q3}_15") (pintype "output"))
      (node (ref "IC21") (pin "3") (pinfunction "~{Q0}_3") (pintype "output"))
      (node (ref "IC21") (pin "9") (pinfunction "~{Q1}_9") (pintype "output"))
      (node (ref "IC24") (pin "12") (pinfunction "~{Q2}_12") (pintype "output"))
      (node (ref "IC24") (pin "15") (pinfunction "~{Q3}_15") (pintype "output"))
      (node (ref "IC24") (pin "3") (pinfunction "~{Q0}_3") (pintype "output"))
      (node (ref "IC24") (pin "9") (pinfunction "~{Q1}_9") (pintype "output"))
      (node (ref "IC25") (pin "12") (pinfunction "~{Q2}_12") (pintype "output"))
      (node (ref "IC25") (pin "15") (pinfunction "~{Q3}_15") (pintype "output"))
      (node (ref "IC25") (pin "3") (pinfunction "~{Q0}_3") (pintype "output"))
      (node (ref "IC25") (pin "9") (pinfunction "~{Q1}_9") (pintype "output"))
      (node (ref "IC28") (pin "12") (pinfunction "~{Q2}_12") (pintype "output"))
      (node (ref "IC28") (pin "15") (pinfunction "~{Q3}_15") (pintype "output"))
      (node (ref "IC28") (pin "3") (pinfunction "~{Q0}_3") (pintype "output"))
      (node (ref "IC28") (pin "9") (pinfunction "~{Q1}_9") (pintype "output"))
      (node (ref "IC29") (pin "12") (pinfunction "~{Q2}_12") (pintype "output"))
      (node (ref "IC29") (pin "15") (pinfunction "~{Q3}_15") (pintype "output"))
      (node (ref "IC29") (pin "3") (pinfunction "~{Q0}_3") (pintype "output"))
      (node (ref "IC29") (pin "9") (pinfunction "~{Q1}_9") (pintype "output"))
      (node (ref "IC32") (pin "12") (pinfunction "~{Q2}_12") (pintype "output"))
      (node (ref "IC32") (pin "15") (pinfunction "~{Q3}_15") (pintype "output"))
      (node (ref "IC32") (pin "3") (pinfunction "~{Q0}_3") (pintype "output"))
      (node (ref "IC32") (pin "9") (pinfunction "~{Q1}_9") (pintype "output"))
      (node (ref "IC33") (pin "12") (pinfunction "~{Q2}_12") (pintype "output"))
      (node (ref "IC33") (pin "15") (pinfunction "~{Q3}_15") (pintype "output"))
      (node (ref "IC33") (pin "3") (pinfunction "~{Q0}_3") (pintype "output"))
      (node (ref "IC33") (pin "9") (pinfunction "~{Q1}_9") (pintype "output"))
      (node (ref "IC36") (pin "12") (pinfunction "~{Q2}_12") (pintype "output"))
      (node (ref "IC36") (pin "15") (pinfunction "~{Q3}_15") (pintype "output"))
      (node (ref "IC36") (pin "3") (pinfunction "~{Q0}_3") (pintype "output"))
      (node (ref "IC36") (pin "9") (pinfunction "~{Q1}_9") (pintype "output"))
      (node (ref "IC37") (pin "12") (pinfunction "~{Q2}_12") (pintype "output"))
      (node (ref "IC37") (pin "15") (pinfunction "~{Q3}_15") (pintype "output"))
      (node (ref "IC37") (pin "3") (pinfunction "~{Q0}_3") (pintype "output"))
      (node (ref "IC37") (pin "9") (pinfunction "~{Q1}_9") (pintype "output"))
      (node (ref "IC4") (pin "12") (pinfunction "~{Q2}_12") (pintype "output"))
      (node (ref "IC4") (pin "15") (pinfunction "~{Q3}_15") (pintype "output"))
      (node (ref "IC4") (pin "3") (pinfunction "~{Q0}_3") (pintype "output"))
      (node (ref "IC4") (pin "9") (pinfunction "~{Q1}_9") (pintype "output"))
      (node (ref "IC40") (pin "12") (pinfunction "~{Q2}_12") (pintype "output"))
      (node (ref "IC40") (pin "15") (pinfunction "~{Q3}_15") (pintype "output"))
      (node (ref "IC40") (pin "3") (pinfunction "~{Q0}_3") (pintype "output"))
      (node (ref "IC40") (pin "9") (pinfunction "~{Q1}_9") (pintype "output"))
      (node (ref "IC41") (pin "12") (pinfunction "~{Q2}_12") (pintype "output"))
      (node (ref "IC41") (pin "15") (pinfunction "~{Q3}_15") (pintype "output"))
      (node (ref "IC41") (pin "3") (pinfunction "~{Q0}_3") (pintype "output"))
      (node (ref "IC41") (pin "9") (pinfunction "~{Q1}_9") (pintype "output"))
      (node (ref "IC44") (pin "12") (pinfunction "~{Q2}_12") (pintype "output"))
      (node (ref "IC44") (pin "15") (pinfunction "~{Q3}_15") (pintype "output"))
      (node (ref "IC44") (pin "3") (pinfunction "~{Q0}_3") (pintype "output"))
      (node (ref "IC44") (pin "9") (pinfunction "~{Q1}_9") (pintype "output"))
      (node (ref "IC45") (pin "12") (pinfunction "~{Q2}_12") (pintype "output"))
      (node (ref "IC45") (pin "15") (pinfunction "~{Q3}_15") (pintype "output"))
      (node (ref "IC45") (pin "3") (pinfunction "~{Q0}_3") (pintype "output"))
      (node (ref "IC45") (pin "9") (pinfunction "~{Q1}_9") (pintype "output"))
      (node (ref "IC48") (pin "12") (pinfunction "~{Q2}_12") (pintype "output"))
      (node (ref "IC48") (pin "15") (pinfunction "~{Q3}_15") (pintype "output"))
      (node (ref "IC48") (pin "3") (pinfunction "~{Q0}_3") (pintype "output"))
      (node (ref "IC48") (pin "9") (pinfunction "~{Q1}_9") (pintype "output"))
      (node (ref "IC49") (pin "12") (pinfunction "~{Q2}_12") (pintype "output"))
      (node (ref "IC49") (pin "15") (pinfunction "~{Q3}_15") (pintype "output"))
      (node (ref "IC49") (pin "3") (pinfunction "~{Q0}_3") (pintype "output"))
      (node (ref "IC49") (pin "9") (pinfunction "~{Q1}_9") (pintype "output"))
      (node (ref "IC5") (pin "12") (pinfunction "~{Q2}_12") (pintype "output"))
      (node (ref "IC5") (pin "15") (pinfunction "~{Q3}_15") (pintype "output"))
      (node (ref "IC5") (pin "3") (pinfunction "~{Q0}_3") (pintype "output"))
      (node (ref "IC5") (pin "9") (pinfunction "~{Q1}_9") (pintype "output"))
      (node (ref "IC52") (pin "12") (pinfunction "~{Q2}_12") (pintype "output"))
      (node (ref "IC52") (pin "15") (pinfunction "~{Q3}_15") (pintype "output"))
      (node (ref "IC52") (pin "3") (pinfunction "~{Q0}_3") (pintype "output"))
      (node (ref "IC52") (pin "9") (pinfunction "~{Q1}_9") (pintype "output"))
      (node (ref "IC53") (pin "12") (pinfunction "~{Q2}_12") (pintype "output"))
      (node (ref "IC53") (pin "15") (pinfunction "~{Q3}_15") (pintype "output"))
      (node (ref "IC53") (pin "3") (pinfunction "~{Q0}_3") (pintype "output"))
      (node (ref "IC53") (pin "9") (pinfunction "~{Q1}_9") (pintype "output"))
      (node (ref "IC56") (pin "12") (pinfunction "~{Q2}_12") (pintype "output"))
      (node (ref "IC56") (pin "15") (pinfunction "~{Q3}_15") (pintype "output"))
      (node (ref "IC56") (pin "3") (pinfunction "~{Q0}_3") (pintype "output"))
      (node (ref "IC56") (pin "9") (pinfunction "~{Q1}_9") (pintype "output"))
      (node (ref "IC57") (pin "12") (pinfunction "~{Q2}_12") (pintype "output"))
      (node (ref "IC57") (pin "15") (pinfunction "~{Q3}_15") (pintype "output"))
      (node (ref "IC57") (pin "3") (pinfunction "~{Q0}_3") (pintype "output"))
      (node (ref "IC57") (pin "9") (pinfunction "~{Q1}_9") (pintype "output"))
      (node (ref "IC60") (pin "12") (pinfunction "~{Q2}_12") (pintype "output"))
      (node (ref "IC60") (pin "15") (pinfunction "~{Q3}_15") (pintype "output"))
      (node (ref "IC60") (pin "3") (pinfunction "~{Q0}_3") (pintype "output"))
      (node (ref "IC60") (pin "9") (pinfunction "~{Q1}_9") (pintype "output"))
      (node (ref "IC61") (pin "12") (pinfunction "~{Q2}_12") (pintype "output"))
      (node (ref "IC61") (pin "15") (pinfunction "~{Q3}_15") (pintype "output"))
      (node (ref "IC61") (pin "3") (pinfunction "~{Q0}_3") (pintype "output"))
      (node (ref "IC61") (pin "9") (pinfunction "~{Q1}_9") (pintype "output"))
      (node (ref "IC64") (pin "12") (pinfunction "~{Q2}_12") (pintype "output"))
      (node (ref "IC64") (pin "15") (pinfunction "~{Q3}_15") (pintype "output"))
      (node (ref "IC64") (pin "3") (pinfunction "~{Q0}_3") (pintype "output"))
      (node (ref "IC64") (pin "9") (pinfunction "~{Q1}_9") (pintype "output"))
      (node (ref "IC8") (pin "12") (pinfunction "~{Q2}_12") (pintype "output"))
      (node (ref "IC8") (pin "15") (pinfunction "~{Q3}_15") (pintype "output"))
      (node (ref "IC8") (pin "3") (pinfunction "~{Q0}_3") (pintype "output"))
      (node (ref "IC8") (pin "9") (pinfunction "~{Q1}_9") (pintype "output"))
      (node (ref "IC9") (pin "12") (pinfunction "~{Q2}_12") (pintype "output"))
      (node (ref "IC9") (pin "15") (pinfunction "~{Q3}_15") (pintype "output"))
      (node (ref "IC9") (pin "3") (pinfunction "~{Q0}_3") (pintype "output"))
      (node (ref "IC9") (pin "9") (pinfunction "~{Q1}_9") (pintype "output"))
      (node (ref "KICK_DRUM") (pin "3") (pinfunction "3_3") (pintype "passive"))
      (node (ref "KNOB_CONNECTIONS") (pin "49") (pinfunction "49_49") (pintype "passive"))
      (node (ref "LO_TOM") (pin "3") (pinfunction "3_3") (pintype "passive"))
      (node (ref "POWER_SUPPY") (pin "2") (pinfunction "2_2") (pintype "passive"))
      (node (ref "POWER_SUPPY") (pin "3") (pinfunction "3_3") (pintype "passive"))
      (node (ref "R11") (pin "1") (pinfunction "1_1") (pintype "passive"))
      (node (ref "R13") (pin "1") (pinfunction "1_1") (pintype "passive"))
      (node (ref "R15") (pin "1") (pinfunction "1_1") (pintype "passive"))
      (node (ref "R17") (pin "1") (pinfunction "1_1") (pintype "passive"))
      (node (ref "R18") (pin "1") (pinfunction "1_1") (pintype "passive"))
      (node (ref "R20") (pin "1") (pinfunction "1_1") (pintype "passive"))
      (node (ref "R22") (pin "1") (pinfunction "1_1") (pintype "passive"))
      (node (ref "R24") (pin "1") (pinfunction "1_1") (pintype "passive"))
      (node (ref "R26") (pin "1") (pinfunction "1_1") (pintype "passive"))
      (node (ref "R28") (pin "1") (pinfunction "1_1") (pintype "passive"))
      (node (ref "R3") (pin "1") (pinfunction "1_1") (pintype "passive"))
      (node (ref "R30") (pin "1") (pinfunction "1_1") (pintype "passive"))
      (node (ref "R32") (pin "1") (pinfunction "1_1") (pintype "passive"))
      (node (ref "R5") (pin "1") (pinfunction "1_1") (pintype "passive"))
      (node (ref "R7") (pin "1") (pinfunction "1_1") (pintype "passive"))
      (node (ref "R9") (pin "1") (pinfunction "1_1") (pintype "passive"))
      (node (ref "SEQUENCER") (pin "17") (pinfunction "17_17") (pintype "passive"))
      (node (ref "SNARE_DRUM") (pin "3") (pinfunction "3_3") (pintype "passive"))
      (node (ref "SPECIAL_INSTRUMENT") (pin "3") (pinfunction "3_3") (pintype "passive"))
    )
    (net (code "3") (name "Net-(1B-1)") (class "Default")
      (node (ref "1") (pin "2") (pinfunction "1_2") (pintype "passive"))
      (node (ref "KNOB_CONNECTIONS") (pin "43") (pinfunction "43_43") (pintype "passive"))
      (node (ref "KNOB_CONNECTIONS") (pin "45") (pinfunction "45_45") (pintype "passive"))
      (node (ref "KNOB_CONNECTIONS") (pin "47") (pinfunction "47_47") (pintype "passive"))
      (node (ref "SEQUENCER") (pin "15") (pinfunction "15_15") (pintype "passive"))
    )
    (net (code "4") (name "Net-(1C-1)") (class "Default")
      (node (ref "1") (pin "3") (pinfunction "1_3") (pintype "passive"))
      (node (ref "KNOB_CONNECTIONS") (pin "37") (pinfunction "37_37") (pintype "passive"))
      (node (ref "KNOB_CONNECTIONS") (pin "39") (pinfunction "39_39") (pintype "passive"))
      (node (ref "KNOB_CONNECTIONS") (pin "41") (pinfunction "41_41") (pintype "passive"))
      (node (ref "SEQUENCER") (pin "13") (pinfunction "13_13") (pintype "passive"))
    )
    (net (code "5") (name "Net-(1D-1)") (class "Default")
      (node (ref "1") (pin "4") (pinfunction "1_4") (pintype "passive"))
      (node (ref "KNOB_CONNECTIONS") (pin "31") (pinfunction "31_31") (pintype "passive"))
      (node (ref "KNOB_CONNECTIONS") (pin "33") (pinfunction "33_33") (pintype "passive"))
      (node (ref "KNOB_CONNECTIONS") (pin "35") (pinfunction "35_35") (pintype "passive"))
      (node (ref "SEQUENCER") (pin "11") (pinfunction "11_11") (pintype "passive"))
    )
    (net (code "6") (name "Net-(1E-1)") (class "Default")
      (node (ref "1") (pin "5") (pinfunction "1_5") (pintype "passive"))
      (node (ref "KNOB_CONNECTIONS") (pin "25") (pinfunction "25_25") (pintype "passive"))
      (node (ref "KNOB_CONNECTIONS") (pin "27") (pinfunction "27_27") (pintype "passive"))
      (node (ref "KNOB_CONNECTIONS") (pin "29") (pinfunction "29_29") (pintype "passive"))
      (node (ref "SEQUENCER") (pin "9") (pinfunction "9_9") (pintype "passive"))
    )
    (net (code "7") (name "Net-(2-Pad1)") (class "Default")
      (node (ref "2") (pin "1") (pinfunction "1_1") (pintype "passive"))
      (node (ref "KNOB_CONNECTIONS") (pin "19") (pinfunction "19_19") (pintype "passive"))
      (node (ref "KNOB_CONNECTIONS") (pin "21") (pinfunction "21_21") (pintype "passive"))
      (node (ref "KNOB_CONNECTIONS") (pin "23") (pinfunction "23_23") (pintype "passive"))
      (node (ref "SEQUENCER") (pin "7") (pinfunction "7_7") (pintype "passive"))
    )
    (net (code "8") (name "Net-(2B-1)") (class "Default")
      (node (ref "2") (pin "2") (pinfunction "1_2") (pintype "passive"))
      (node (ref "KNOB_CONNECTIONS") (pin "13") (pinfunction "13_13") (pintype "passive"))
      (node (ref "KNOB_CONNECTIONS") (pin "15") (pinfunction "15_15") (pintype "passive"))
      (node (ref "KNOB_CONNECTIONS") (pin "17") (pinfunction "17_17") (pintype "passive"))
      (node (ref "SEQUENCER") (pin "5") (pinfunction "5_5") (pintype "passive"))
    )
    (net (code "9") (name "Net-(2C-1)") (class "Default")
      (node (ref "2") (pin "3") (pinfunction "1_3") (pintype "passive"))
      (node (ref "KNOB_CONNECTIONS") (pin "11") (pinfunction "11_11") (pintype "passive"))
      (node (ref "KNOB_CONNECTIONS") (pin "7") (pinfunction "7_7") (pintype "passive"))
      (node (ref "KNOB_CONNECTIONS") (pin "9") (pinfunction "9_9") (pintype "passive"))
      (node (ref "SEQUENCER") (pin "3") (pinfunction "3_3") (pintype "passive"))
    )
    (net (code "10") (name "Net-(2D-1)") (class "Default")
      (node (ref "2") (pin "4") (pinfunction "1_4") (pintype "passive"))
      (node (ref "KNOB_CONNECTIONS") (pin "1") (pinfunction "1_1") (pintype "passive"))
      (node (ref "KNOB_CONNECTIONS") (pin "3") (pinfunction "3_3") (pintype "passive"))
      (node (ref "KNOB_CONNECTIONS") (pin "5") (pinfunction "5_5") (pintype "passive"))
      (node (ref "SEQUENCER") (pin "1") (pinfunction "1_1") (pintype "passive"))
    )
    (net (code "11") (name "Net-(BUTTON_1-Pad2)") (class "Default")
      (node (ref "BUTTON_1") (pin "2") (pinfunction "2_2") (pintype "passive"))
      (node (ref "R1") (pin "1") (pinfunction "1_1") (pintype "passive"))
    )
    (net (code "12") (name "Net-(BUTTON_2-Pad2)") (class "Default")
      (node (ref "BUTTON_2") (pin "2") (pinfunction "2_2") (pintype "passive"))
      (node (ref "R2") (pin "1") (pinfunction "1_1") (pintype "passive"))
    )
    (net (code "13") (name "Net-(BUTTON_3-Pad2)") (class "Default")
      (node (ref "BUTTON_3") (pin "2") (pinfunction "2_2") (pintype "passive"))
      (node (ref "R4") (pin "1") (pinfunction "1_1") (pintype "passive"))
    )
    (net (code "14") (name "Net-(BUTTON_4-Pad2)") (class "Default")
      (node (ref "BUTTON_4") (pin "2") (pinfunction "2_2") (pintype "passive"))
      (node (ref "R6") (pin "1") (pinfunction "1_1") (pintype "passive"))
    )
    (net (code "15") (name "Net-(BUTTON_5-Pad2)") (class "Default")
      (node (ref "BUTTON_5") (pin "2") (pinfunction "2_2") (pintype "passive"))
      (node (ref "R8") (pin "1") (pinfunction "1_1") (pintype "passive"))
    )
    (net (code "16") (name "Net-(BUTTON_6-Pad2)") (class "Default")
      (node (ref "BUTTON_6") (pin "2") (pinfunction "2_2") (pintype "passive"))
      (node (ref "R10") (pin "1") (pinfunction "1_1") (pintype "passive"))
    )
    (net (code "17") (name "Net-(BUTTON_7-Pad2)") (class "Default")
      (node (ref "BUTTON_7") (pin "2") (pinfunction "2_2") (pintype "passive"))
      (node (ref "R12") (pin "1") (pinfunction "1_1") (pintype "passive"))
    )
    (net (code "18") (name "Net-(BUTTON_8-Pad2)") (class "Default")
      (node (ref "BUTTON_8") (pin "2") (pinfunction "2_2") (pintype "passive"))
      (node (ref "R14") (pin "1") (pinfunction "1_1") (pintype "passive"))
    )
    (net (code "19") (name "Net-(BUTTON_9-Pad2)") (class "Default")
      (node (ref "BUTTON_9") (pin "2") (pinfunction "2_2") (pintype "passive"))
      (node (ref "R16") (pin "1") (pinfunction "1_1") (pintype "passive"))
    )
    (net (code "20") (name "Net-(BUTTON_10-Pad2)") (class "Default")
      (node (ref "BUTTON_10") (pin "2") (pinfunction "2_2") (pintype "passive"))
      (node (ref "R19") (pin "1") (pinfunction "1_1") (pintype "passive"))
    )
    (net (code "21") (name "Net-(BUTTON_11-Pad2)") (class "Default")
      (node (ref "BUTTON_11") (pin "2") (pinfunction "2_2") (pintype "passive"))
      (node (ref "R21") (pin "1") (pinfunction "1_1") (pintype "passive"))
    )
    (net (code "22") (name "Net-(BUTTON_12-Pad2)") (class "Default")
      (node (ref "BUTTON_12") (pin "2") (pinfunction "2_2") (pintype "passive"))
      (node (ref "R23") (pin "1") (pinfunction "1_1") (pintype "passive"))
    )
    (net (code "23") (name "Net-(BUTTON_13-Pad2)") (class "Default")
      (node (ref "BUTTON_13") (pin "2") (pinfunction "2_2") (pintype "passive"))
      (node (ref "R25") (pin "1") (pinfunction "1_1") (pintype "passive"))
    )
    (net (code "24") (name "Net-(BUTTON_14-Pad2)") (class "Default")
      (node (ref "BUTTON_14") (pin "2") (pinfunction "2_2") (pintype "passive"))
      (node (ref "R27") (pin "1") (pinfunction "1_1") (pintype "passive"))
    )
    (net (code "25") (name "Net-(BUTTON_15-Pad2)") (class "Default")
      (node (ref "BUTTON_15") (pin "2") (pinfunction "2_2") (pintype "passive"))
      (node (ref "R29") (pin "1") (pinfunction "1_1") (pintype "passive"))
    )
    (net (code "26") (name "Net-(BUTTON_16-Pad2)") (class "Default")
      (node (ref "BUTTON_16") (pin "2") (pinfunction "2_2") (pintype "passive"))
      (node (ref "R31") (pin "1") (pinfunction "1_1") (pintype "passive"))
    )
    (net (code "27") (name "Net-(CLOSED_HI_HAT-Pad1)") (class "Default")
      (node (ref "CLOSED_HI_HAT") (pin "1") (pinfunction "1_1") (pintype "passive"))
      (node (ref "KNOB_CONNECTIONS") (pin "38") (pinfunction "38_38") (pintype "passive"))
      (node (ref "KNOB_CONNECTIONS") (pin "40") (pinfunction "40_40") (pintype "passive"))
      (node (ref "KNOB_CONNECTIONS") (pin "42") (pinfunction "42_42") (pintype "passive"))
      (node (ref "PIN_CONNECTIONS") (pin "14") (pinfunction "14_14") (pintype "passive"))
    )
    (net (code "28") (name "Net-(CLOSED_HI_HAT-Pad2)") (class "Default")
      (node (ref "CLOSED_HI_HAT") (pin "2") (pinfunction "2_2") (pintype "passive"))
      (node (ref "CLOSED_HI_HAT") (pin "4") (pinfunction "4_4") (pintype "passive"))
      (node (ref "MIXER") (pin "7") (pinfunction "7_7") (pintype "passive"))
    )
    (net (code "29") (name "Net-(CRASH-Pad1)") (class "Default")
      (node (ref "CRASH") (pin "1") (pinfunction "1_1") (pintype "passive"))
      (node (ref "KNOB_CONNECTIONS") (pin "26") (pinfunction "26_26") (pintype "passive"))
      (node (ref "KNOB_CONNECTIONS") (pin "28") (pinfunction "28_28") (pintype "passive"))
      (node (ref "KNOB_CONNECTIONS") (pin "30") (pinfunction "30_30") (pintype "passive"))
      (node (ref "PIN_CONNECTIONS") (pin "10") (pinfunction "10_10") (pintype "passive"))
    )
    (net (code "30") (name "Net-(CRASH-Pad2)") (class "Default")
      (node (ref "CRASH") (pin "2") (pinfunction "2_2") (pintype "passive"))
      (node (ref "CRASH") (pin "4") (pinfunction "4_4") (pintype "passive"))
      (node (ref "MIXER") (pin "5") (pinfunction "5_5") (pintype "passive"))
    )
    (net (code "31") (name "Net-(HI_HAT-Pad1)") (class "Default")
      (node (ref "HI_HAT") (pin "1") (pinfunction "1_1") (pintype "passive"))
      (node (ref "KNOB_CONNECTIONS") (pin "32") (pinfunction "32_32") (pintype "passive"))
      (node (ref "KNOB_CONNECTIONS") (pin "34") (pinfunction "34_34") (pintype "passive"))
      (node (ref "KNOB_CONNECTIONS") (pin "36") (pinfunction "36_36") (pintype "passive"))
      (node (ref "PIN_CONNECTIONS") (pin "12") (pinfunction "12_12") (pintype "passive"))
    )
    (net (code "32") (name "Net-(HI_HAT-Pad2)") (class "Default")
      (node (ref "HI_HAT") (pin "2") (pinfunction "2_2") (pintype "passive"))
      (node (ref "HI_HAT") (pin "4") (pinfunction "4_4") (pintype "passive"))
      (node (ref "MIXER") (pin "6") (pinfunction "6_6") (pintype "passive"))
    )
    (net (code "33") (name "Net-(HI_TOM-Pad1)") (class "Default")
      (node (ref "HI_TOM") (pin "1") (pinfunction "1_1") (pintype "passive"))
      (node (ref "KNOB_CONNECTIONS") (pin "10") (pinfunction "10_10") (pintype "passive"))
      (node (ref "KNOB_CONNECTIONS") (pin "12") (pinfunction "12_12") (pintype "passive"))
      (node (ref "KNOB_CONNECTIONS") (pin "8") (pinfunction "8_8") (pintype "passive"))
      (node (ref "PIN_CONNECTIONS") (pin "4") (pinfunction "4_4") (pintype "passive"))
    )
    (net (code "34") (name "Net-(HI_TOM-Pad2)") (class "Default")
      (node (ref "HI_TOM") (pin "2") (pinfunction "2_2") (pintype "passive"))
      (node (ref "HI_TOM") (pin "4") (pinfunction "4_4") (pintype "passive"))
      (node (ref "MIXER") (pin "2") (pinfunction "2_2") (pintype "passive"))
    )
    (net (code "35") (name "Net-(IC1A-D0)") (class "Default")
      (node (ref "C2") (pin "1") (pinfunction "1_1") (pintype "passive"))
      (node (ref "IC1") (pin "13") (pinfunction "D2_13") (pintype "input"))
      (node (ref "IC1") (pin "14") (pinfunction "D3_14") (pintype "input"))
      (node (ref "IC1") (pin "4") (pinfunction "D0_4") (pintype "input"))
      (node (ref "IC1") (pin "6") (pinfunction "POL_6") (pintype "input"))
      (node (ref "IC1") (pin "7") (pinfunction "D1_7") (pintype "input"))
      (node (ref "R1") (pin "2") (pinfunction "2_2") (pintype "passive"))
      (node (ref "R17") (pin "2") (pinfunction "2_2") (pintype "passive"))
    )
    (net (code "36") (name "Net-(IC1A-Q0)") (class "Default")
      (node (ref "IC1") (pin "1") (pinfunction "Q3_1") (pintype "output"))
      (node (ref "IC1") (pin "10") (pinfunction "Q1_10") (pintype "output"))
      (node (ref "IC1") (pin "11") (pinfunction "Q2_11") (pintype "output"))
      (node (ref "IC1") (pin "2") (pinfunction "Q0_2") (pintype "output"))
      (node (ref "IC2") (pin "13") (pinfunction "D2_13") (pintype "input"))
      (node (ref "IC2") (pin "14") (pinfunction "D3_14") (pintype "input"))
      (node (ref "IC2") (pin "4") (pinfunction "D0_4") (pintype "input"))
      (node (ref "IC2") (pin "6") (pinfunction "POL_6") (pintype "input"))
      (node (ref "IC2") (pin "7") (pinfunction "D1_7") (pintype "input"))
    )
    (net (code "37") (name "Net-(IC2A-Q0)") (class "Default")
      (node (ref "IC2") (pin "1") (pinfunction "Q3_1") (pintype "output"))
      (node (ref "IC2") (pin "10") (pinfunction "Q1_10") (pintype "output"))
      (node (ref "IC2") (pin "11") (pinfunction "Q2_11") (pintype "output"))
      (node (ref "IC2") (pin "2") (pinfunction "Q0_2") (pintype "output"))
      (node (ref "IC3") (pin "1") (pinfunction "I0_1") (pintype "input"))
    )
    (net (code "38") (name "Net-(IC2A-~{Q0})") (class "Default")
      (node (ref "IC2") (pin "12") (pinfunction "~{Q2}_12") (pintype "output"))
      (node (ref "IC2") (pin "15") (pinfunction "~{Q3}_15") (pintype "output"))
      (node (ref "IC2") (pin "3") (pinfunction "~{Q0}_3") (pintype "output"))
      (node (ref "IC2") (pin "9") (pinfunction "~{Q1}_9") (pintype "output"))
      (node (ref "IC4") (pin "13") (pinfunction "D2_13") (pintype "input"))
      (node (ref "IC4") (pin "14") (pinfunction "D3_14") (pintype "input"))
      (node (ref "IC4") (pin "4") (pinfunction "D0_4") (pintype "input"))
      (node (ref "IC4") (pin "6") (pinfunction "POL_6") (pintype "input"))
      (node (ref "IC4") (pin "7") (pinfunction "D1_7") (pintype "input"))
    )
    (net (code "39") (name "Net-(IC3A-I1)") (class "Default")
      (node (ref "IC3") (pin "2") (pinfunction "I1_2") (pintype "input"))
      (node (ref "IC4") (pin "1") (pinfunction "Q3_1") (pintype "output"))
      (node (ref "IC4") (pin "10") (pinfunction "Q1_10") (pintype "output"))
      (node (ref "IC4") (pin "11") (pinfunction "Q2_11") (pintype "output"))
      (node (ref "IC4") (pin "2") (pinfunction "Q0_2") (pintype "output"))
    )
    (net (code "40") (name "Net-(IC5A-D0)") (class "Default")
      (node (ref "C3") (pin "1") (pinfunction "1_1") (pintype "passive"))
      (node (ref "IC5") (pin "13") (pinfunction "D2_13") (pintype "input"))
      (node (ref "IC5") (pin "14") (pinfunction "D3_14") (pintype "input"))
      (node (ref "IC5") (pin "4") (pinfunction "D0_4") (pintype "input"))
      (node (ref "IC5") (pin "6") (pinfunction "POL_6") (pintype "input"))
      (node (ref "IC5") (pin "7") (pinfunction "D1_7") (pintype "input"))
      (node (ref "R2") (pin "2") (pinfunction "2_2") (pintype "passive"))
      (node (ref "R3") (pin "2") (pinfunction "2_2") (pintype "passive"))
    )
    (net (code "41") (name "Net-(IC5A-Q0)") (class "Default")
      (node (ref "IC5") (pin "1") (pinfunction "Q3_1") (pintype "output"))
      (node (ref "IC5") (pin "10") (pinfunction "Q1_10") (pintype "output"))
      (node (ref "IC5") (pin "11") (pinfunction "Q2_11") (pintype "output"))
      (node (ref "IC5") (pin "2") (pinfunction "Q0_2") (pintype "output"))
      (node (ref "IC6") (pin "13") (pinfunction "D2_13") (pintype "input"))
      (node (ref "IC6") (pin "14") (pinfunction "D3_14") (pintype "input"))
      (node (ref "IC6") (pin "4") (pinfunction "D0_4") (pintype "input"))
      (node (ref "IC6") (pin "6") (pinfunction "POL_6") (pintype "input"))
      (node (ref "IC6") (pin "7") (pinfunction "D1_7") (pintype "input"))
    )
    (net (code "42") (name "Net-(IC6A-Q0)") (class "Default")
      (node (ref "IC6") (pin "1") (pinfunction "Q3_1") (pintype "output"))
      (node (ref "IC6") (pin "10") (pinfunction "Q1_10") (pintype "output"))
      (node (ref "IC6") (pin "11") (pinfunction "Q2_11") (pintype "output"))
      (node (ref "IC6") (pin "2") (pinfunction "Q0_2") (pintype "output"))
      (node (ref "IC7") (pin "1") (pinfunction "I0_1") (pintype "input"))
    )
    (net (code "43") (name "Net-(IC6A-~{Q0})") (class "Default")
      (node (ref "IC6") (pin "12") (pinfunction "~{Q2}_12") (pintype "output"))
      (node (ref "IC6") (pin "15") (pinfunction "~{Q3}_15") (pintype "output"))
      (node (ref "IC6") (pin "3") (pinfunction "~{Q0}_3") (pintype "output"))
      (node (ref "IC6") (pin "9") (pinfunction "~{Q1}_9") (pintype "output"))
      (node (ref "IC8") (pin "13") (pinfunction "D2_13") (pintype "input"))
      (node (ref "IC8") (pin "14") (pinfunction "D3_14") (pintype "input"))
      (node (ref "IC8") (pin "4") (pinfunction "D0_4") (pintype "input"))
      (node (ref "IC8") (pin "6") (pinfunction "POL_6") (pintype "input"))
      (node (ref "IC8") (pin "7") (pinfunction "D1_7") (pintype "input"))
    )
    (net (code "44") (name "Net-(IC7A-I1)") (class "Default")
      (node (ref "IC7") (pin "2") (pinfunction "I1_2") (pintype "input"))
      (node (ref "IC8") (pin "1") (pinfunction "Q3_1") (pintype "output"))
      (node (ref "IC8") (pin "10") (pinfunction "Q1_10") (pintype "output"))
      (node (ref "IC8") (pin "11") (pinfunction "Q2_11") (pintype "output"))
      (node (ref "IC8") (pin "2") (pinfunction "Q0_2") (pintype "output"))
    )
    (net (code "45") (name "Net-(IC9A-D0)") (class "Default")
      (node (ref "C4") (pin "1") (pinfunction "1_1") (pintype "passive"))
      (node (ref "IC9") (pin "13") (pinfunction "D2_13") (pintype "input"))
      (node (ref "IC9") (pin "14") (pinfunction "D3_14") (pintype "input"))
      (node (ref "IC9") (pin "4") (pinfunction "D0_4") (pintype "input"))
      (node (ref "IC9") (pin "6") (pinfunction "POL_6") (pintype "input"))
      (node (ref "IC9") (pin "7") (pinfunction "D1_7") (pintype "input"))
      (node (ref "R4") (pin "2") (pinfunction "2_2") (pintype "passive"))
      (node (ref "R5") (pin "2") (pinfunction "2_2") (pintype "passive"))
    )
    (net (code "46") (name "Net-(IC10A-D0)") (class "Default")
      (node (ref "IC10") (pin "13") (pinfunction "D2_13") (pintype "input"))
      (node (ref "IC10") (pin "14") (pinfunction "D3_14") (pintype "input"))
      (node (ref "IC10") (pin "4") (pinfunction "D0_4") (pintype "input"))
      (node (ref "IC10") (pin "6") (pinfunction "POL_6") (pintype "input"))
      (node (ref "IC10") (pin "7") (pinfunction "D1_7") (pintype "input"))
      (node (ref "IC9") (pin "1") (pinfunction "Q3_1") (pintype "output"))
      (node (ref "IC9") (pin "10") (pinfunction "Q1_10") (pintype "output"))
      (node (ref "IC9") (pin "11") (pinfunction "Q2_11") (pintype "output"))
      (node (ref "IC9") (pin "2") (pinfunction "Q0_2") (pintype "output"))
    )
    (net (code "47") (name "Net-(IC10A-Q0)") (class "Default")
      (node (ref "IC10") (pin "1") (pinfunction "Q3_1") (pintype "output"))
      (node (ref "IC10") (pin "10") (pinfunction "Q1_10") (pintype "output"))
      (node (ref "IC10") (pin "11") (pinfunction "Q2_11") (pintype "output"))
      (node (ref "IC10") (pin "2") (pinfunction "Q0_2") (pintype "output"))
      (node (ref "IC11") (pin "1") (pinfunction "I0_1") (pintype "input"))
    )
    (net (code "48") (name "Net-(IC10A-~{Q0})") (class "Default")
      (node (ref "IC10") (pin "12") (pinfunction "~{Q2}_12") (pintype "output"))
      (node (ref "IC10") (pin "15") (pinfunction "~{Q3}_15") (pintype "output"))
      (node (ref "IC10") (pin "3") (pinfunction "~{Q0}_3") (pintype "output"))
      (node (ref "IC10") (pin "9") (pinfunction "~{Q1}_9") (pintype "output"))
      (node (ref "IC12") (pin "13") (pinfunction "D2_13") (pintype "input"))
      (node (ref "IC12") (pin "14") (pinfunction "D3_14") (pintype "input"))
      (node (ref "IC12") (pin "4") (pinfunction "D0_4") (pintype "input"))
      (node (ref "IC12") (pin "6") (pinfunction "POL_6") (pintype "input"))
      (node (ref "IC12") (pin "7") (pinfunction "D1_7") (pintype "input"))
    )
    (net (code "49") (name "Net-(IC11A-I1)") (class "Default")
      (node (ref "IC11") (pin "2") (pinfunction "I1_2") (pintype "input"))
      (node (ref "IC12") (pin "1") (pinfunction "Q3_1") (pintype "output"))
      (node (ref "IC12") (pin "10") (pinfunction "Q1_10") (pintype "output"))
      (node (ref "IC12") (pin "11") (pinfunction "Q2_11") (pintype "output"))
      (node (ref "IC12") (pin "2") (pinfunction "Q0_2") (pintype "output"))
    )
    (net (code "50") (name "Net-(IC13A-D0)") (class "Default")
      (node (ref "C5") (pin "1") (pinfunction "1_1") (pintype "passive"))
      (node (ref "IC13") (pin "13") (pinfunction "D2_13") (pintype "input"))
      (node (ref "IC13") (pin "14") (pinfunction "D3_14") (pintype "input"))
      (node (ref "IC13") (pin "4") (pinfunction "D0_4") (pintype "input"))
      (node (ref "IC13") (pin "6") (pinfunction "POL_6") (pintype "input"))
      (node (ref "IC13") (pin "7") (pinfunction "D1_7") (pintype "input"))
      (node (ref "R6") (pin "2") (pinfunction "2_2") (pintype "passive"))
      (node (ref "R7") (pin "2") (pinfunction "2_2") (pintype "passive"))
    )
    (net (code "51") (name "Net-(IC13A-Q0)") (class "Default")
      (node (ref "IC13") (pin "1") (pinfunction "Q3_1") (pintype "output"))
      (node (ref "IC13") (pin "10") (pinfunction "Q1_10") (pintype "output"))
      (node (ref "IC13") (pin "11") (pinfunction "Q2_11") (pintype "output"))
      (node (ref "IC13") (pin "2") (pinfunction "Q0_2") (pintype "output"))
      (node (ref "IC14") (pin "13") (pinfunction "D2_13") (pintype "input"))
      (node (ref "IC14") (pin "14") (pinfunction "D3_14") (pintype "input"))
      (node (ref "IC14") (pin "4") (pinfunction "D0_4") (pintype "input"))
      (node (ref "IC14") (pin "6") (pinfunction "POL_6") (pintype "input"))
      (node (ref "IC14") (pin "7") (pinfunction "D1_7") (pintype "input"))
    )
    (net (code "52") (name "Net-(IC14A-Q0)") (class "Default")
      (node (ref "IC14") (pin "1") (pinfunction "Q3_1") (pintype "output"))
      (node (ref "IC14") (pin "10") (pinfunction "Q1_10") (pintype "output"))
      (node (ref "IC14") (pin "11") (pinfunction "Q2_11") (pintype "output"))
      (node (ref "IC14") (pin "2") (pinfunction "Q0_2") (pintype "output"))
      (node (ref "IC15") (pin "1") (pinfunction "I0_1") (pintype "input"))
    )
    (net (code "53") (name "Net-(IC14A-~{Q0})") (class "Default")
      (node (ref "IC14") (pin "12") (pinfunction "~{Q2}_12") (pintype "output"))
      (node (ref "IC14") (pin "15") (pinfunction "~{Q3}_15") (pintype "output"))
      (node (ref "IC14") (pin "3") (pinfunction "~{Q0}_3") (pintype "output"))
      (node (ref "IC14") (pin "9") (pinfunction "~{Q1}_9") (pintype "output"))
      (node (ref "IC16") (pin "13") (pinfunction "D2_13") (pintype "input"))
      (node (ref "IC16") (pin "14") (pinfunction "D3_14") (pintype "input"))
      (node (ref "IC16") (pin "4") (pinfunction "D0_4") (pintype "input"))
      (node (ref "IC16") (pin "6") (pinfunction "POL_6") (pintype "input"))
      (node (ref "IC16") (pin "7") (pinfunction "D1_7") (pintype "input"))
    )
    (net (code "54") (name "Net-(IC15A-I1)") (class "Default")
      (node (ref "IC15") (pin "2") (pinfunction "I1_2") (pintype "input"))
      (node (ref "IC16") (pin "1") (pinfunction "Q3_1") (pintype "output"))
      (node (ref "IC16") (pin "10") (pinfunction "Q1_10") (pintype "output"))
      (node (ref "IC16") (pin "11") (pinfunction "Q2_11") (pintype "output"))
      (node (ref "IC16") (pin "2") (pinfunction "Q0_2") (pintype "output"))
    )
    (net (code "55") (name "Net-(IC17A-D0)") (class "Default")
      (node (ref "C6") (pin "1") (pinfunction "1_1") (pintype "passive"))
      (node (ref "IC17") (pin "13") (pinfunction "D2_13") (pintype "input"))
      (node (ref "IC17") (pin "14") (pinfunction "D3_14") (pintype "input"))
      (node (ref "IC17") (pin "4") (pinfunction "D0_4") (pintype "input"))
      (node (ref "IC17") (pin "6") (pinfunction "POL_6") (pintype "input"))
      (node (ref "IC17") (pin "7") (pinfunction "D1_7") (pintype "input"))
      (node (ref "R8") (pin "2") (pinfunction "2_2") (pintype "passive"))
      (node (ref "R9") (pin "2") (pinfunction "2_2") (pintype "passive"))
    )
    (net (code "56") (name "Net-(IC17A-Q0)") (class "Default")
      (node (ref "IC17") (pin "1") (pinfunction "Q3_1") (pintype "output"))
      (node (ref "IC17") (pin "10") (pinfunction "Q1_10") (pintype "output"))
      (node (ref "IC17") (pin "11") (pinfunction "Q2_11") (pintype "output"))
      (node (ref "IC17") (pin "2") (pinfunction "Q0_2") (pintype "output"))
      (node (ref "IC18") (pin "13") (pinfunction "D2_13") (pintype "input"))
      (node (ref "IC18") (pin "14") (pinfunction "D3_14") (pintype "input"))
      (node (ref "IC18") (pin "4") (pinfunction "D0_4") (pintype "input"))
      (node (ref "IC18") (pin "6") (pinfunction "POL_6") (pintype "input"))
      (node (ref "IC18") (pin "7") (pinfunction "D1_7") (pintype "input"))
    )
    (net (code "57") (name "Net-(IC18A-Q0)") (class "Default")
      (node (ref "IC18") (pin "1") (pinfunction "Q3_1") (pintype "output"))
      (node (ref "IC18") (pin "10") (pinfunction "Q1_10") (pintype "output"))
      (node (ref "IC18") (pin "11") (pinfunction "Q2_11") (pintype "output"))
      (node (ref "IC18") (pin "2") (pinfunction "Q0_2") (pintype "output"))
      (node (ref "IC19") (pin "1") (pinfunction "I0_1") (pintype "input"))
    )
    (net (code "58") (name "Net-(IC18A-~{Q0})") (class "Default")
      (node (ref "IC18") (pin "12") (pinfunction "~{Q2}_12") (pintype "output"))
      (node (ref "IC18") (pin "15") (pinfunction "~{Q3}_15") (pintype "output"))
      (node (ref "IC18") (pin "3") (pinfunction "~{Q0}_3") (pintype "output"))
      (node (ref "IC18") (pin "9") (pinfunction "~{Q1}_9") (pintype "output"))
      (node (ref "IC20") (pin "13") (pinfunction "D2_13") (pintype "input"))
      (node (ref "IC20") (pin "14") (pinfunction "D3_14") (pintype "input"))
      (node (ref "IC20") (pin "4") (pinfunction "D0_4") (pintype "input"))
      (node (ref "IC20") (pin "6") (pinfunction "POL_6") (pintype "input"))
      (node (ref "IC20") (pin "7") (pinfunction "D1_7") (pintype "input"))
    )
    (net (code "59") (name "Net-(IC19A-I1)") (class "Default")
      (node (ref "IC19") (pin "2") (pinfunction "I1_2") (pintype "input"))
      (node (ref "IC20") (pin "1") (pinfunction "Q3_1") (pintype "output"))
      (node (ref "IC20") (pin "10") (pinfunction "Q1_10") (pintype "output"))
      (node (ref "IC20") (pin "11") (pinfunction "Q2_11") (pintype "output"))
      (node (ref "IC20") (pin "2") (pinfunction "Q0_2") (pintype "output"))
    )
    (net (code "60") (name "Net-(IC21A-D0)") (class "Default")
      (node (ref "C7") (pin "1") (pinfunction "1_1") (pintype "passive"))
      (node (ref "IC21") (pin "13") (pinfunction "D2_13") (pintype "input"))
      (node (ref "IC21") (pin "14") (pinfunction "D3_14") (pintype "input"))
      (node (ref "IC21") (pin "4") (pinfunction "D0_4") (pintype "input"))
      (node (ref "IC21") (pin "6") (pinfunction "POL_6") (pintype "input"))
      (node (ref "IC21") (pin "7") (pinfunction "D1_7") (pintype "input"))
      (node (ref "R10") (pin "2") (pinfunction "2_2") (pintype "passive"))
      (node (ref "R11") (pin "2") (pinfunction "2_2") (pintype "passive"))
    )
    (net (code "61") (name "Net-(IC21A-Q0)") (class "Default")
      (node (ref "IC21") (pin "1") (pinfunction "Q3_1") (pintype "output"))
      (node (ref "IC21") (pin "10") (pinfunction "Q1_10") (pintype "output"))
      (node (ref "IC21") (pin "11") (pinfunction "Q2_11") (pintype "output"))
      (node (ref "IC21") (pin "2") (pinfunction "Q0_2") (pintype "output"))
      (node (ref "IC22") (pin "13") (pinfunction "D2_13") (pintype "input"))
      (node (ref "IC22") (pin "14") (pinfunction "D3_14") (pintype "input"))
      (node (ref "IC22") (pin "4") (pinfunction "D0_4") (pintype "input"))
      (node (ref "IC22") (pin "6") (pinfunction "POL_6") (pintype "input"))
      (node (ref "IC22") (pin "7") (pinfunction "D1_7") (pintype "input"))
    )
    (net (code "62") (name "Net-(IC22A-Q0)") (class "Default")
      (node (ref "IC22") (pin "1") (pinfunction "Q3_1") (pintype "output"))
      (node (ref "IC22") (pin "10") (pinfunction "Q1_10") (pintype "output"))
      (node (ref "IC22") (pin "11") (pinfunction "Q2_11") (pintype "output"))
      (node (ref "IC22") (pin "2") (pinfunction "Q0_2") (pintype "output"))
      (node (ref "IC23") (pin "1") (pinfunction "I0_1") (pintype "input"))
    )
    (net (code "63") (name "Net-(IC22A-~{Q0})") (class "Default")
      (node (ref "IC22") (pin "12") (pinfunction "~{Q2}_12") (pintype "output"))
      (node (ref "IC22") (pin "15") (pinfunction "~{Q3}_15") (pintype "output"))
      (node (ref "IC22") (pin "3") (pinfunction "~{Q0}_3") (pintype "output"))
      (node (ref "IC22") (pin "9") (pinfunction "~{Q1}_9") (pintype "output"))
      (node (ref "IC24") (pin "13") (pinfunction "D2_13") (pintype "input"))
      (node (ref "IC24") (pin "14") (pinfunction "D3_14") (pintype "input"))
      (node (ref "IC24") (pin "4") (pinfunction "D0_4") (pintype "input"))
      (node (ref "IC24") (pin "6") (pinfunction "POL_6") (pintype "input"))
      (node (ref "IC24") (pin "7") (pinfunction "D1_7") (pintype "input"))
    )
    (net (code "64") (name "Net-(IC23A-I1)") (class "Default")
      (node (ref "IC23") (pin "2") (pinfunction "I1_2") (pintype "input"))
      (node (ref "IC24") (pin "1") (pinfunction "Q3_1") (pintype "output"))
      (node (ref "IC24") (pin "10") (pinfunction "Q1_10") (pintype "output"))
      (node (ref "IC24") (pin "11") (pinfunction "Q2_11") (pintype "output"))
      (node (ref "IC24") (pin "2") (pinfunction "Q0_2") (pintype "output"))
    )
    (net (code "65") (name "Net-(IC25A-D0)") (class "Default")
      (node (ref "C8") (pin "1") (pinfunction "1_1") (pintype "passive"))
      (node (ref "IC25") (pin "13") (pinfunction "D2_13") (pintype "input"))
      (node (ref "IC25") (pin "14") (pinfunction "D3_14") (pintype "input"))
      (node (ref "IC25") (pin "4") (pinfunction "D0_4") (pintype "input"))
      (node (ref "IC25") (pin "6") (pinfunction "POL_6") (pintype "input"))
      (node (ref "IC25") (pin "7") (pinfunction "D1_7") (pintype "input"))
      (node (ref "R12") (pin "2") (pinfunction "2_2") (pintype "passive"))
      (node (ref "R13") (pin "2") (pinfunction "2_2") (pintype "passive"))
    )
    (net (code "66") (name "Net-(IC25A-Q0)") (class "Default")
      (node (ref "IC25") (pin "1") (pinfunction "Q3_1") (pintype "output"))
      (node (ref "IC25") (pin "10") (pinfunction "Q1_10") (pintype "output"))
      (node (ref "IC25") (pin "11") (pinfunction "Q2_11") (pintype "output"))
      (node (ref "IC25") (pin "2") (pinfunction "Q0_2") (pintype "output"))
      (node (ref "IC26") (pin "13") (pinfunction "D2_13") (pintype "input"))
      (node (ref "IC26") (pin "14") (pinfunction "D3_14") (pintype "input"))
      (node (ref "IC26") (pin "4") (pinfunction "D0_4") (pintype "input"))
      (node (ref "IC26") (pin "6") (pinfunction "POL_6") (pintype "input"))
      (node (ref "IC26") (pin "7") (pinfunction "D1_7") (pintype "input"))
    )
    (net (code "67") (name "Net-(IC26A-Q0)") (class "Default")
      (node (ref "IC26") (pin "1") (pinfunction "Q3_1") (pintype "output"))
      (node (ref "IC26") (pin "10") (pinfunction "Q1_10") (pintype "output"))
      (node (ref "IC26") (pin "11") (pinfunction "Q2_11") (pintype "output"))
      (node (ref "IC26") (pin "2") (pinfunction "Q0_2") (pintype "output"))
      (node (ref "IC27") (pin "1") (pinfunction "I0_1") (pintype "input"))
    )
    (net (code "68") (name "Net-(IC26A-~{Q0})") (class "Default")
      (node (ref "IC26") (pin "12") (pinfunction "~{Q2}_12") (pintype "output"))
      (node (ref "IC26") (pin "15") (pinfunction "~{Q3}_15") (pintype "output"))
      (node (ref "IC26") (pin "3") (pinfunction "~{Q0}_3") (pintype "output"))
      (node (ref "IC26") (pin "9") (pinfunction "~{Q1}_9") (pintype "output"))
      (node (ref "IC28") (pin "13") (pinfunction "D2_13") (pintype "input"))
      (node (ref "IC28") (pin "14") (pinfunction "D3_14") (pintype "input"))
      (node (ref "IC28") (pin "4") (pinfunction "D0_4") (pintype "input"))
      (node (ref "IC28") (pin "6") (pinfunction "POL_6") (pintype "input"))
      (node (ref "IC28") (pin "7") (pinfunction "D1_7") (pintype "input"))
    )
    (net (code "69") (name "Net-(IC27A-I1)") (class "Default")
      (node (ref "IC27") (pin "2") (pinfunction "I1_2") (pintype "input"))
      (node (ref "IC28") (pin "1") (pinfunction "Q3_1") (pintype "output"))
      (node (ref "IC28") (pin "10") (pinfunction "Q1_10") (pintype "output"))
      (node (ref "IC28") (pin "11") (pinfunction "Q2_11") (pintype "output"))
      (node (ref "IC28") (pin "2") (pinfunction "Q0_2") (pintype "output"))
    )
    (net (code "70") (name "Net-(IC29A-D0)") (class "Default")
      (node (ref "C9") (pin "1") (pinfunction "1_1") (pintype "passive"))
      (node (ref "IC29") (pin "13") (pinfunction "D2_13") (pintype "input"))
      (node (ref "IC29") (pin "14") (pinfunction "D3_14") (pintype "input"))
      (node (ref "IC29") (pin "4") (pinfunction "D0_4") (pintype "input"))
      (node (ref "IC29") (pin "6") (pinfunction "POL_6") (pintype "input"))
      (node (ref "IC29") (pin "7") (pinfunction "D1_7") (pintype "input"))
      (node (ref "R14") (pin "2") (pinfunction "2_2") (pintype "passive"))
      (node (ref "R15") (pin "2") (pinfunction "2_2") (pintype "passive"))
    )
    (net (code "71") (name "Net-(IC29A-Q0)") (class "Default")
      (node (ref "IC29") (pin "1") (pinfunction "Q3_1") (pintype "output"))
      (node (ref "IC29") (pin "10") (pinfunction "Q1_10") (pintype "output"))
      (node (ref "IC29") (pin "11") (pinfunction "Q2_11") (pintype "output"))
      (node (ref "IC29") (pin "2") (pinfunction "Q0_2") (pintype "output"))
      (node (ref "IC30") (pin "13") (pinfunction "D2_13") (pintype "input"))
      (node (ref "IC30") (pin "14") (pinfunction "D3_14") (pintype "input"))
      (node (ref "IC30") (pin "4") (pinfunction "D0_4") (pintype "input"))
      (node (ref "IC30") (pin "6") (pinfunction "POL_6") (pintype "input"))
      (node (ref "IC30") (pin "7") (pinfunction "D1_7") (pintype "input"))
    )
    (net (code "72") (name "Net-(IC30A-Q0)") (class "Default")
      (node (ref "IC30") (pin "1") (pinfunction "Q3_1") (pintype "output"))
      (node (ref "IC30") (pin "10") (pinfunction "Q1_10") (pintype "output"))
      (node (ref "IC30") (pin "11") (pinfunction "Q2_11") (pintype "output"))
      (node (ref "IC30") (pin "2") (pinfunction "Q0_2") (pintype "output"))
      (node (ref "IC31") (pin "1") (pinfunction "I0_1") (pintype "input"))
    )
    (net (code "73") (name "Net-(IC30A-~{Q0})") (class "Default")
      (node (ref "IC30") (pin "12") (pinfunction "~{Q2}_12") (pintype "output"))
      (node (ref "IC30") (pin "15") (pinfunction "~{Q3}_15") (pintype "output"))
      (node (ref "IC30") (pin "3") (pinfunction "~{Q0}_3") (pintype "output"))
      (node (ref "IC30") (pin "9") (pinfunction "~{Q1}_9") (pintype "output"))
      (node (ref "IC32") (pin "13") (pinfunction "D2_13") (pintype "input"))
      (node (ref "IC32") (pin "14") (pinfunction "D3_14") (pintype "input"))
      (node (ref "IC32") (pin "4") (pinfunction "D0_4") (pintype "input"))
      (node (ref "IC32") (pin "6") (pinfunction "POL_6") (pintype "input"))
      (node (ref "IC32") (pin "7") (pinfunction "D1_7") (pintype "input"))
    )
    (net (code "74") (name "Net-(IC31A-I1)") (class "Default")
      (node (ref "IC31") (pin "2") (pinfunction "I1_2") (pintype "input"))
      (node (ref "IC32") (pin "1") (pinfunction "Q3_1") (pintype "output"))
      (node (ref "IC32") (pin "10") (pinfunction "Q1_10") (pintype "output"))
      (node (ref "IC32") (pin "11") (pinfunction "Q2_11") (pintype "output"))
      (node (ref "IC32") (pin "2") (pinfunction "Q0_2") (pintype "output"))
    )
    (net (code "75") (name "Net-(IC33A-D0)") (class "Default")
      (node (ref "C10") (pin "1") (pinfunction "1_1") (pintype "passive"))
      (node (ref "IC33") (pin "13") (pinfunction "D2_13") (pintype "input"))
      (node (ref "IC33") (pin "14") (pinfunction "D3_14") (pintype "input"))
      (node (ref "IC33") (pin "4") (pinfunction "D0_4") (pintype "input"))
      (node (ref "IC33") (pin "6") (pinfunction "POL_6") (pintype "input"))
      (node (ref "IC33") (pin "7") (pinfunction "D1_7") (pintype "input"))
      (node (ref "R16") (pin "2") (pinfunction "2_2") (pintype "passive"))
      (node (ref "R18") (pin "2") (pinfunction "2_2") (pintype "passive"))
    )
    (net (code "76") (name "Net-(IC33A-Q0)") (class "Default")
      (node (ref "IC33") (pin "1") (pinfunction "Q3_1") (pintype "output"))
      (node (ref "IC33") (pin "10") (pinfunction "Q1_10") (pintype "output"))
      (node (ref "IC33") (pin "11") (pinfunction "Q2_11") (pintype "output"))
      (node (ref "IC33") (pin "2") (pinfunction "Q0_2") (pintype "output"))
      (node (ref "IC34") (pin "13") (pinfunction "D2_13") (pintype "input"))
      (node (ref "IC34") (pin "14") (pinfunction "D3_14") (pintype "input"))
      (node (ref "IC34") (pin "4") (pinfunction "D0_4") (pintype "input"))
      (node (ref "IC34") (pin "6") (pinfunction "POL_6") (pintype "input"))
      (node (ref "IC34") (pin "7") (pinfunction "D1_7") (pintype "input"))
    )
    (net (code "77") (name "Net-(IC34A-Q0)") (class "Default")
      (node (ref "IC34") (pin "1") (pinfunction "Q3_1") (pintype "output"))
      (node (ref "IC34") (pin "10") (pinfunction "Q1_10") (pintype "output"))
      (node (ref "IC34") (pin "11") (pinfunction "Q2_11") (pintype "output"))
      (node (ref "IC34") (pin "2") (pinfunction "Q0_2") (pintype "output"))
      (node (ref "IC35") (pin "1") (pinfunction "I0_1") (pintype "input"))
    )
    (net (code "78") (name "Net-(IC34A-~{Q0})") (class "Default")
      (node (ref "IC34") (pin "12") (pinfunction "~{Q2}_12") (pintype "output"))
      (node (ref "IC34") (pin "15") (pinfunction "~{Q3}_15") (pintype "output"))
      (node (ref "IC34") (pin "3") (pinfunction "~{Q0}_3") (pintype "output"))
      (node (ref "IC34") (pin "9") (pinfunction "~{Q1}_9") (pintype "output"))
      (node (ref "IC36") (pin "13") (pinfunction "D2_13") (pintype "input"))
      (node (ref "IC36") (pin "14") (pinfunction "D3_14") (pintype "input"))
      (node (ref "IC36") (pin "4") (pinfunction "D0_4") (pintype "input"))
      (node (ref "IC36") (pin "6") (pinfunction "POL_6") (pintype "input"))
      (node (ref "IC36") (pin "7") (pinfunction "D1_7") (pintype "input"))
    )
    (net (code "79") (name "Net-(IC35A-I1)") (class "Default")
      (node (ref "IC35") (pin "2") (pinfunction "I1_2") (pintype "input"))
      (node (ref "IC36") (pin "1") (pinfunction "Q3_1") (pintype "output"))
      (node (ref "IC36") (pin "10") (pinfunction "Q1_10") (pintype "output"))
      (node (ref "IC36") (pin "11") (pinfunction "Q2_11") (pintype "output"))
      (node (ref "IC36") (pin "2") (pinfunction "Q0_2") (pintype "output"))
    )
    (net (code "80") (name "Net-(IC37A-D0)") (class "Default")
      (node (ref "C11") (pin "1") (pinfunction "1_1") (pintype "passive"))
      (node (ref "IC37") (pin "13") (pinfunction "D2_13") (pintype "input"))
      (node (ref "IC37") (pin "14") (pinfunction "D3_14") (pintype "input"))
      (node (ref "IC37") (pin "4") (pinfunction "D0_4") (pintype "input"))
      (node (ref "IC37") (pin "6") (pinfunction "POL_6") (pintype "input"))
      (node (ref "IC37") (pin "7") (pinfunction "D1_7") (pintype "input"))
      (node (ref "R19") (pin "2") (pinfunction "2_2") (pintype "passive"))
      (node (ref "R20") (pin "2") (pinfunction "2_2") (pintype "passive"))
    )
    (net (code "81") (name "Net-(IC37A-Q0)") (class "Default")
      (node (ref "IC37") (pin "1") (pinfunction "Q3_1") (pintype "output"))
      (node (ref "IC37") (pin "10") (pinfunction "Q1_10") (pintype "output"))
      (node (ref "IC37") (pin "11") (pinfunction "Q2_11") (pintype "output"))
      (node (ref "IC37") (pin "2") (pinfunction "Q0_2") (pintype "output"))
      (node (ref "IC38") (pin "13") (pinfunction "D2_13") (pintype "input"))
      (node (ref "IC38") (pin "14") (pinfunction "D3_14") (pintype "input"))
      (node (ref "IC38") (pin "4") (pinfunction "D0_4") (pintype "input"))
      (node (ref "IC38") (pin "6") (pinfunction "POL_6") (pintype "input"))
      (node (ref "IC38") (pin "7") (pinfunction "D1_7") (pintype "input"))
    )
    (net (code "82") (name "Net-(IC38A-Q0)") (class "Default")
      (node (ref "IC38") (pin "1") (pinfunction "Q3_1") (pintype "output"))
      (node (ref "IC38") (pin "10") (pinfunction "Q1_10") (pintype "output"))
      (node (ref "IC38") (pin "11") (pinfunction "Q2_11") (pintype "output"))
      (node (ref "IC38") (pin "2") (pinfunction "Q0_2") (pintype "output"))
      (node (ref "IC39") (pin "1") (pinfunction "I0_1") (pintype "input"))
    )
    (net (code "83") (name "Net-(IC38A-~{Q0})") (class "Default")
      (node (ref "IC38") (pin "12") (pinfunction "~{Q2}_12") (pintype "output"))
      (node (ref "IC38") (pin "15") (pinfunction "~{Q3}_15") (pintype "output"))
      (node (ref "IC38") (pin "3") (pinfunction "~{Q0}_3") (pintype "output"))
      (node (ref "IC38") (pin "9") (pinfunction "~{Q1}_9") (pintype "output"))
      (node (ref "IC40") (pin "13") (pinfunction "D2_13") (pintype "input"))
      (node (ref "IC40") (pin "14") (pinfunction "D3_14") (pintype "input"))
      (node (ref "IC40") (pin "4") (pinfunction "D0_4") (pintype "input"))
      (node (ref "IC40") (pin "6") (pinfunction "POL_6") (pintype "input"))
      (node (ref "IC40") (pin "7") (pinfunction "D1_7") (pintype "input"))
    )
    (net (code "84") (name "Net-(IC39A-I1)") (class "Default")
      (node (ref "IC39") (pin "2") (pinfunction "I1_2") (pintype "input"))
      (node (ref "IC40") (pin "1") (pinfunction "Q3_1") (pintype "output"))
      (node (ref "IC40") (pin "10") (pinfunction "Q1_10") (pintype "output"))
      (node (ref "IC40") (pin "11") (pinfunction "Q2_11") (pintype "output"))
      (node (ref "IC40") (pin "2") (pinfunction "Q0_2") (pintype "output"))
    )
    (net (code "85") (name "Net-(IC41A-D0)") (class "Default")
      (node (ref "C12") (pin "1") (pinfunction "1_1") (pintype "passive"))
      (node (ref "IC41") (pin "13") (pinfunction "D2_13") (pintype "input"))
      (node (ref "IC41") (pin "14") (pinfunction "D3_14") (pintype "input"))
      (node (ref "IC41") (pin "4") (pinfunction "D0_4") (pintype "input"))
      (node (ref "IC41") (pin "6") (pinfunction "POL_6") (pintype "input"))
      (node (ref "IC41") (pin "7") (pinfunction "D1_7") (pintype "input"))
      (node (ref "R21") (pin "2") (pinfunction "2_2") (pintype "passive"))
      (node (ref "R22") (pin "2") (pinfunction "2_2") (pintype "passive"))
    )
    (net (code "86") (name "Net-(IC41A-Q0)") (class "Default")
      (node (ref "IC41") (pin "1") (pinfunction "Q3_1") (pintype "output"))
      (node (ref "IC41") (pin "10") (pinfunction "Q1_10") (pintype "output"))
      (node (ref "IC41") (pin "11") (pinfunction "Q2_11") (pintype "output"))
      (node (ref "IC41") (pin "2") (pinfunction "Q0_2") (pintype "output"))
      (node (ref "IC42") (pin "13") (pinfunction "D2_13") (pintype "input"))
      (node (ref "IC42") (pin "14") (pinfunction "D3_14") (pintype "input"))
      (node (ref "IC42") (pin "4") (pinfunction "D0_4") (pintype "input"))
      (node (ref "IC42") (pin "6") (pinfunction "POL_6") (pintype "input"))
      (node (ref "IC42") (pin "7") (pinfunction "D1_7") (pintype "input"))
    )
    (net (code "87") (name "Net-(IC42A-Q0)") (class "Default")
      (node (ref "IC42") (pin "1") (pinfunction "Q3_1") (pintype "output"))
      (node (ref "IC42") (pin "10") (pinfunction "Q1_10") (pintype "output"))
      (node (ref "IC42") (pin "11") (pinfunction "Q2_11") (pintype "output"))
      (node (ref "IC42") (pin "2") (pinfunction "Q0_2") (pintype "output"))
      (node (ref "IC43") (pin "1") (pinfunction "I0_1") (pintype "input"))
    )
    (net (code "88") (name "Net-(IC42A-~{Q0})") (class "Default")
      (node (ref "IC42") (pin "12") (pinfunction "~{Q2}_12") (pintype "output"))
      (node (ref "IC42") (pin "15") (pinfunction "~{Q3}_15") (pintype "output"))
      (node (ref "IC42") (pin "3") (pinfunction "~{Q0}_3") (pintype "output"))
      (node (ref "IC42") (pin "9") (pinfunction "~{Q1}_9") (pintype "output"))
      (node (ref "IC44") (pin "13") (pinfunction "D2_13") (pintype "input"))
      (node (ref "IC44") (pin "14") (pinfunction "D3_14") (pintype "input"))
      (node (ref "IC44") (pin "4") (pinfunction "D0_4") (pintype "input"))
      (node (ref "IC44") (pin "6") (pinfunction "POL_6") (pintype "input"))
      (node (ref "IC44") (pin "7") (pinfunction "D1_7") (pintype "input"))
    )
    (net (code "89") (name "Net-(IC43A-I1)") (class "Default")
      (node (ref "IC43") (pin "2") (pinfunction "I1_2") (pintype "input"))
      (node (ref "IC44") (pin "1") (pinfunction "Q3_1") (pintype "output"))
      (node (ref "IC44") (pin "10") (pinfunction "Q1_10") (pintype "output"))
      (node (ref "IC44") (pin "11") (pinfunction "Q2_11") (pintype "output"))
      (node (ref "IC44") (pin "2") (pinfunction "Q0_2") (pintype "output"))
    )
    (net (code "90") (name "Net-(IC45A-D0)") (class "Default")
      (node (ref "C13") (pin "1") (pinfunction "1_1") (pintype "passive"))
      (node (ref "IC45") (pin "13") (pinfunction "D2_13") (pintype "input"))
      (node (ref "IC45") (pin "14") (pinfunction "D3_14") (pintype "input"))
      (node (ref "IC45") (pin "4") (pinfunction "D0_4") (pintype "input"))
      (node (ref "IC45") (pin "6") (pinfunction "POL_6") (pintype "input"))
      (node (ref "IC45") (pin "7") (pinfunction "D1_7") (pintype "input"))
      (node (ref "R23") (pin "2") (pinfunction "2_2") (pintype "passive"))
      (node (ref "R24") (pin "2") (pinfunction "2_2") (pintype "passive"))
    )
    (net (code "91") (name "Net-(IC45A-Q0)") (class "Default")
      (node (ref "IC45") (pin "1") (pinfunction "Q3_1") (pintype "output"))
      (node (ref "IC45") (pin "10") (pinfunction "Q1_10") (pintype "output"))
      (node (ref "IC45") (pin "11") (pinfunction "Q2_11") (pintype "output"))
      (node (ref "IC45") (pin "2") (pinfunction "Q0_2") (pintype "output"))
      (node (ref "IC46") (pin "13") (pinfunction "D2_13") (pintype "input"))
      (node (ref "IC46") (pin "14") (pinfunction "D3_14") (pintype "input"))
      (node (ref "IC46") (pin "4") (pinfunction "D0_4") (pintype "input"))
      (node (ref "IC46") (pin "6") (pinfunction "POL_6") (pintype "input"))
      (node (ref "IC46") (pin "7") (pinfunction "D1_7") (pintype "input"))
    )
    (net (code "92") (name "Net-(IC46A-Q0)") (class "Default")
      (node (ref "IC46") (pin "1") (pinfunction "Q3_1") (pintype "output"))
      (node (ref "IC46") (pin "10") (pinfunction "Q1_10") (pintype "output"))
      (node (ref "IC46") (pin "11") (pinfunction "Q2_11") (pintype "output"))
      (node (ref "IC46") (pin "2") (pinfunction "Q0_2") (pintype "output"))
      (node (ref "IC47") (pin "1") (pinfunction "I0_1") (pintype "input"))
    )
    (net (code "93") (name "Net-(IC46A-~{Q0})") (class "Default")
      (node (ref "IC46") (pin "12") (pinfunction "~{Q2}_12") (pintype "output"))
      (node (ref "IC46") (pin "15") (pinfunction "~{Q3}_15") (pintype "output"))
      (node (ref "IC46") (pin "3") (pinfunction "~{Q0}_3") (pintype "output"))
      (node (ref "IC46") (pin "9") (pinfunction "~{Q1}_9") (pintype "output"))
      (node (ref "IC48") (pin "13") (pinfunction "D2_13") (pintype "input"))
      (node (ref "IC48") (pin "14") (pinfunction "D3_14") (pintype "input"))
      (node (ref "IC48") (pin "4") (pinfunction "D0_4") (pintype "input"))
      (node (ref "IC48") (pin "6") (pinfunction "POL_6") (pintype "input"))
      (node (ref "IC48") (pin "7") (pinfunction "D1_7") (pintype "input"))
    )
    (net (code "94") (name "Net-(IC47A-I1)") (class "Default")
      (node (ref "IC47") (pin "2") (pinfunction "I1_2") (pintype "input"))
      (node (ref "IC48") (pin "1") (pinfunction "Q3_1") (pintype "output"))
      (node (ref "IC48") (pin "10") (pinfunction "Q1_10") (pintype "output"))
      (node (ref "IC48") (pin "11") (pinfunction "Q2_11") (pintype "output"))
      (node (ref "IC48") (pin "2") (pinfunction "Q0_2") (pintype "output"))
    )
    (net (code "95") (name "Net-(IC49A-D0)") (class "Default")
      (node (ref "C14") (pin "1") (pinfunction "1_1") (pintype "passive"))
      (node (ref "IC49") (pin "13") (pinfunction "D2_13") (pintype "input"))
      (node (ref "IC49") (pin "14") (pinfunction "D3_14") (pintype "input"))
      (node (ref "IC49") (pin "4") (pinfunction "D0_4") (pintype "input"))
      (node (ref "IC49") (pin "6") (pinfunction "POL_6") (pintype "input"))
      (node (ref "IC49") (pin "7") (pinfunction "D1_7") (pintype "input"))
      (node (ref "R25") (pin "2") (pinfunction "2_2") (pintype "passive"))
      (node (ref "R26") (pin "2") (pinfunction "2_2") (pintype "passive"))
    )
    (net (code "96") (name "Net-(IC49A-Q0)") (class "Default")
      (node (ref "IC49") (pin "1") (pinfunction "Q3_1") (pintype "output"))
      (node (ref "IC49") (pin "10") (pinfunction "Q1_10") (pintype "output"))
      (node (ref "IC49") (pin "11") (pinfunction "Q2_11") (pintype "output"))
      (node (ref "IC49") (pin "2") (pinfunction "Q0_2") (pintype "output"))
      (node (ref "IC50") (pin "13") (pinfunction "D2_13") (pintype "input"))
      (node (ref "IC50") (pin "14") (pinfunction "D3_14") (pintype "input"))
      (node (ref "IC50") (pin "4") (pinfunction "D0_4") (pintype "input"))
      (node (ref "IC50") (pin "6") (pinfunction "POL_6") (pintype "input"))
      (node (ref "IC50") (pin "7") (pinfunction "D1_7") (pintype "input"))
    )
    (net (code "97") (name "Net-(IC50A-Q0)") (class "Default")
      (node (ref "IC50") (pin "1") (pinfunction "Q3_1") (pintype "output"))
      (node (ref "IC50") (pin "10") (pinfunction "Q1_10") (pintype "output"))
      (node (ref "IC50") (pin "11") (pinfunction "Q2_11") (pintype "output"))
      (node (ref "IC50") (pin "2") (pinfunction "Q0_2") (pintype "output"))
      (node (ref "IC51") (pin "1") (pinfunction "I0_1") (pintype "input"))
    )
    (net (code "98") (name "Net-(IC50A-~{Q0})") (class "Default")
      (node (ref "IC50") (pin "12") (pinfunction "~{Q2}_12") (pintype "output"))
      (node (ref "IC50") (pin "15") (pinfunction "~{Q3}_15") (pintype "output"))
      (node (ref "IC50") (pin "3") (pinfunction "~{Q0}_3") (pintype "output"))
      (node (ref "IC50") (pin "9") (pinfunction "~{Q1}_9") (pintype "output"))
      (node (ref "IC52") (pin "13") (pinfunction "D2_13") (pintype "input"))
      (node (ref "IC52") (pin "14") (pinfunction "D3_14") (pintype "input"))
      (node (ref "IC52") (pin "4") (pinfunction "D0_4") (pintype "input"))
      (node (ref "IC52") (pin "6") (pinfunction "POL_6") (pintype "input"))
      (node (ref "IC52") (pin "7") (pinfunction "D1_7") (pintype "input"))
    )
    (net (code "99") (name "Net-(IC51A-I1)") (class "Default")
      (node (ref "IC51") (pin "2") (pinfunction "I1_2") (pintype "input"))
      (node (ref "IC52") (pin "1") (pinfunction "Q3_1") (pintype "output"))
      (node (ref "IC52") (pin "10") (pinfunction "Q1_10") (pintype "output"))
      (node (ref "IC52") (pin "11") (pinfunction "Q2_11") (pintype "output"))
      (node (ref "IC52") (pin "2") (pinfunction "Q0_2") (pintype "output"))
    )
    (net (code "100") (name "Net-(IC53A-D0)") (class "Default")
      (node (ref "C15") (pin "1") (pinfunction "1_1") (pintype "passive"))
      (node (ref "IC53") (pin "13") (pinfunction "D2_13") (pintype "input"))
      (node (ref "IC53") (pin "14") (pinfunction "D3_14") (pintype "input"))
      (node (ref "IC53") (pin "4") (pinfunction "D0_4") (pintype "input"))
      (node (ref "IC53") (pin "6") (pinfunction "POL_6") (pintype "input"))
      (node (ref "IC53") (pin "7") (pinfunction "D1_7") (pintype "input"))
      (node (ref "R27") (pin "2") (pinfunction "2_2") (pintype "passive"))
      (node (ref "R28") (pin "2") (pinfunction "2_2") (pintype "passive"))
    )
    (net (code "101") (name "Net-(IC53A-Q0)") (class "Default")
      (node (ref "IC53") (pin "1") (pinfunction "Q3_1") (pintype "output"))
      (node (ref "IC53") (pin "10") (pinfunction "Q1_10") (pintype "output"))
      (node (ref "IC53") (pin "11") (pinfunction "Q2_11") (pintype "output"))
      (node (ref "IC53") (pin "2") (pinfunction "Q0_2") (pintype "output"))
      (node (ref "IC54") (pin "13") (pinfunction "D2_13") (pintype "input"))
      (node (ref "IC54") (pin "14") (pinfunction "D3_14") (pintype "input"))
      (node (ref "IC54") (pin "4") (pinfunction "D0_4") (pintype "input"))
      (node (ref "IC54") (pin "6") (pinfunction "POL_6") (pintype "input"))
      (node (ref "IC54") (pin "7") (pinfunction "D1_7") (pintype "input"))
    )
    (net (code "102") (name "Net-(IC54A-Q0)") (class "Default")
      (node (ref "IC54") (pin "1") (pinfunction "Q3_1") (pintype "output"))
      (node (ref "IC54") (pin "10") (pinfunction "Q1_10") (pintype "output"))
      (node (ref "IC54") (pin "11") (pinfunction "Q2_11") (pintype "output"))
      (node (ref "IC54") (pin "2") (pinfunction "Q0_2") (pintype "output"))
      (node (ref "IC55") (pin "1") (pinfunction "I0_1") (pintype "input"))
    )
    (net (code "103") (name "Net-(IC54A-~{Q0})") (class "Default")
      (node (ref "IC54") (pin "12") (pinfunction "~{Q2}_12") (pintype "output"))
      (node (ref "IC54") (pin "15") (pinfunction "~{Q3}_15") (pintype "output"))
      (node (ref "IC54") (pin "3") (pinfunction "~{Q0}_3") (pintype "output"))
      (node (ref "IC54") (pin "9") (pinfunction "~{Q1}_9") (pintype "output"))
      (node (ref "IC56") (pin "13") (pinfunction "D2_13") (pintype "input"))
      (node (ref "IC56") (pin "14") (pinfunction "D3_14") (pintype "input"))
      (node (ref "IC56") (pin "4") (pinfunction "D0_4") (pintype "input"))
      (node (ref "IC56") (pin "6") (pinfunction "POL_6") (pintype "input"))
      (node (ref "IC56") (pin "7") (pinfunction "D1_7") (pintype "input"))
    )
    (net (code "104") (name "Net-(IC55A-I1)") (class "Default")
      (node (ref "IC55") (pin "2") (pinfunction "I1_2") (pintype "input"))
      (node (ref "IC56") (pin "1") (pinfunction "Q3_1") (pintype "output"))
      (node (ref "IC56") (pin "10") (pinfunction "Q1_10") (pintype "output"))
      (node (ref "IC56") (pin "11") (pinfunction "Q2_11") (pintype "output"))
      (node (ref "IC56") (pin "2") (pinfunction "Q0_2") (pintype "output"))
    )
    (net (code "105") (name "Net-(IC57A-D0)") (class "Default")
      (node (ref "C16") (pin "1") (pinfunction "1_1") (pintype "passive"))
      (node (ref "IC57") (pin "13") (pinfunction "D2_13") (pintype "input"))
      (node (ref "IC57") (pin "14") (pinfunction "D3_14") (pintype "input"))
      (node (ref "IC57") (pin "4") (pinfunction "D0_4") (pintype "input"))
      (node (ref "IC57") (pin "6") (pinfunction "POL_6") (pintype "input"))
      (node (ref "IC57") (pin "7") (pinfunction "D1_7") (pintype "input"))
      (node (ref "R29") (pin "2") (pinfunction "2_2") (pintype "passive"))
      (node (ref "R30") (pin "2") (pinfunction "2_2") (pintype "passive"))
    )
    (net (code "106") (name "Net-(IC57A-Q0)") (class "Default")
      (node (ref "IC57") (pin "1") (pinfunction "Q3_1") (pintype "output"))
      (node (ref "IC57") (pin "10") (pinfunction "Q1_10") (pintype "output"))
      (node (ref "IC57") (pin "11") (pinfunction "Q2_11") (pintype "output"))
      (node (ref "IC57") (pin "2") (pinfunction "Q0_2") (pintype "output"))
      (node (ref "IC58") (pin "13") (pinfunction "D2_13") (pintype "input"))
      (node (ref "IC58") (pin "14") (pinfunction "D3_14") (pintype "input"))
      (node (ref "IC58") (pin "4") (pinfunction "D0_4") (pintype "input"))
      (node (ref "IC58") (pin "6") (pinfunction "POL_6") (pintype "input"))
      (node (ref "IC58") (pin "7") (pinfunction "D1_7") (pintype "input"))
    )
    (net (code "107") (name "Net-(IC58A-Q0)") (class "Default")
      (node (ref "IC58") (pin "1") (pinfunction "Q3_1") (pintype "output"))
      (node (ref "IC58") (pin "10") (pinfunction "Q1_10") (pintype "output"))
      (node (ref "IC58") (pin "11") (pinfunction "Q2_11") (pintype "output"))
      (node (ref "IC58") (pin "2") (pinfunction "Q0_2") (pintype "output"))
      (node (ref "IC59") (pin "1") (pinfunction "I0_1") (pintype "input"))
    )
    (net (code "108") (name "Net-(IC58A-~{Q0})") (class "Default")
      (node (ref "IC58") (pin "12") (pinfunction "~{Q2}_12") (pintype "output"))
      (node (ref "IC58") (pin "15") (pinfunction "~{Q3}_15") (pintype "output"))
      (node (ref "IC58") (pin "3") (pinfunction "~{Q0}_3") (pintype "output"))
      (node (ref "IC58") (pin "9") (pinfunction "~{Q1}_9") (pintype "output"))
      (node (ref "IC60") (pin "13") (pinfunction "D2_13") (pintype "input"))
      (node (ref "IC60") (pin "14") (pinfunction "D3_14") (pintype "input"))
      (node (ref "IC60") (pin "4") (pinfunction "D0_4") (pintype "input"))
      (node (ref "IC60") (pin "6") (pinfunction "POL_6") (pintype "input"))
      (node (ref "IC60") (pin "7") (pinfunction "D1_7") (pintype "input"))
    )
    (net (code "109") (name "Net-(IC59A-I1)") (class "Default")
      (node (ref "IC59") (pin "2") (pinfunction "I1_2") (pintype "input"))
      (node (ref "IC60") (pin "1") (pinfunction "Q3_1") (pintype "output"))
      (node (ref "IC60") (pin "10") (pinfunction "Q1_10") (pintype "output"))
      (node (ref "IC60") (pin "11") (pinfunction "Q2_11") (pintype "output"))
      (node (ref "IC60") (pin "2") (pinfunction "Q0_2") (pintype "output"))
    )
    (net (code "110") (name "Net-(IC61A-D0)") (class "Default")
      (node (ref "C17") (pin "1") (pinfunction "1_1") (pintype "passive"))
      (node (ref "IC61") (pin "13") (pinfunction "D2_13") (pintype "input"))
      (node (ref "IC61") (pin "14") (pinfunction "D3_14") (pintype "input"))
      (node (ref "IC61") (pin "4") (pinfunction "D0_4") (pintype "input"))
      (node (ref "IC61") (pin "6") (pinfunction "POL_6") (pintype "input"))
      (node (ref "IC61") (pin "7") (pinfunction "D1_7") (pintype "input"))
      (node (ref "R31") (pin "2") (pinfunction "2_2") (pintype "passive"))
      (node (ref "R32") (pin "2") (pinfunction "2_2") (pintype "passive"))
    )
    (net (code "111") (name "Net-(IC61A-Q0)") (class "Default")
      (node (ref "IC61") (pin "1") (pinfunction "Q3_1") (pintype "output"))
      (node (ref "IC61") (pin "10") (pinfunction "Q1_10") (pintype "output"))
      (node (ref "IC61") (pin "11") (pinfunction "Q2_11") (pintype "output"))
      (node (ref "IC61") (pin "2") (pinfunction "Q0_2") (pintype "output"))
      (node (ref "IC62") (pin "13") (pinfunction "D2_13") (pintype "input"))
      (node (ref "IC62") (pin "14") (pinfunction "D3_14") (pintype "input"))
      (node (ref "IC62") (pin "4") (pinfunction "D0_4") (pintype "input"))
      (node (ref "IC62") (pin "6") (pinfunction "POL_6") (pintype "input"))
      (node (ref "IC62") (pin "7") (pinfunction "D1_7") (pintype "input"))
    )
    (net (code "112") (name "Net-(IC62A-Q0)") (class "Default")
      (node (ref "IC62") (pin "1") (pinfunction "Q3_1") (pintype "output"))
      (node (ref "IC62") (pin "10") (pinfunction "Q1_10") (pintype "output"))
      (node (ref "IC62") (pin "11") (pinfunction "Q2_11") (pintype "output"))
      (node (ref "IC62") (pin "2") (pinfunction "Q0_2") (pintype "output"))
      (node (ref "IC63") (pin "1") (pinfunction "I0_1") (pintype "input"))
    )
    (net (code "113") (name "Net-(IC62A-~{Q0})") (class "Default")
      (node (ref "IC62") (pin "12") (pinfunction "~{Q2}_12") (pintype "output"))
      (node (ref "IC62") (pin "15") (pinfunction "~{Q3}_15") (pintype "output"))
      (node (ref "IC62") (pin "3") (pinfunction "~{Q0}_3") (pintype "output"))
      (node (ref "IC62") (pin "9") (pinfunction "~{Q1}_9") (pintype "output"))
      (node (ref "IC64") (pin "13") (pinfunction "D2_13") (pintype "input"))
      (node (ref "IC64") (pin "14") (pinfunction "D3_14") (pintype "input"))
      (node (ref "IC64") (pin "4") (pinfunction "D0_4") (pintype "input"))
      (node (ref "IC64") (pin "6") (pinfunction "POL_6") (pintype "input"))
      (node (ref "IC64") (pin "7") (pinfunction "D1_7") (pintype "input"))
    )
    (net (code "114") (name "Net-(IC63A-I1)") (class "Default")
      (node (ref "IC63") (pin "2") (pinfunction "I1_2") (pintype "input"))
      (node (ref "IC64") (pin "1") (pinfunction "Q3_1") (pintype "output"))
      (node (ref "IC64") (pin "10") (pinfunction "Q1_10") (pintype "output"))
      (node (ref "IC64") (pin "11") (pinfunction "Q2_11") (pintype "output"))
      (node (ref "IC64") (pin "2") (pinfunction "Q0_2") (pintype "output"))
    )
    (net (code "115") (name "Net-(KICK_DRUM-Pad1)") (class "Default")
      (node (ref "KICK_DRUM") (pin "1") (pinfunction "1_1") (pintype "passive"))
      (node (ref "KNOB_CONNECTIONS") (pin "2") (pinfunction "2_2") (pintype "passive"))
      (node (ref "KNOB_CONNECTIONS") (pin "4") (pinfunction "4_4") (pintype "passive"))
      (node (ref "KNOB_CONNECTIONS") (pin "6") (pinfunction "6_6") (pintype "passive"))
      (node (ref "PIN_CONNECTIONS") (pin "2") (pinfunction "2_2") (pintype "passive"))
    )
    (net (code "116") (name "Net-(KICK_DRUM-Pad2)") (class "Default")
      (node (ref "KICK_DRUM") (pin "2") (pinfunction "2_2") (pintype "passive"))
      (node (ref "KICK_DRUM") (pin "4") (pinfunction "4_4") (pintype "passive"))
      (node (ref "MIXER") (pin "1") (pinfunction "1_1") (pintype "passive"))
    )
    (net (code "117") (name "Net-(KNOB_CONNECTIONS-Pad14)") (class "Default")
      (node (ref "KNOB_CONNECTIONS") (pin "14") (pinfunction "14_14") (pintype "passive"))
      (node (ref "KNOB_CONNECTIONS") (pin "16") (pinfunction "16_16") (pintype "passive"))
      (node (ref "KNOB_CONNECTIONS") (pin "18") (pinfunction "18_18") (pintype "passive"))
      (node (ref "LO_TOM") (pin "1") (pinfunction "1_1") (pintype "passive"))
      (node (ref "PIN_CONNECTIONS") (pin "6") (pinfunction "6_6") (pintype "passive"))
    )
    (net (code "118") (name "Net-(KNOB_CONNECTIONS-Pad20)") (class "Default")
      (node (ref "KNOB_CONNECTIONS") (pin "20") (pinfunction "20_20") (pintype "passive"))
      (node (ref "KNOB_CONNECTIONS") (pin "22") (pinfunction "22_22") (pintype "passive"))
      (node (ref "KNOB_CONNECTIONS") (pin "24") (pinfunction "24_24") (pintype "passive"))
      (node (ref "PIN_CONNECTIONS") (pin "8") (pinfunction "8_8") (pintype "passive"))
      (node (ref "SNARE_DRUM") (pin "1") (pinfunction "1_1") (pintype "passive"))
    )
    (net (code "119") (name "Net-(KNOB_CONNECTIONS-Pad44)") (class "Default")
      (node (ref "KNOB_CONNECTIONS") (pin "44") (pinfunction "44_44") (pintype "passive"))
      (node (ref "KNOB_CONNECTIONS") (pin "46") (pinfunction "46_46") (pintype "passive"))
      (node (ref "KNOB_CONNECTIONS") (pin "48") (pinfunction "48_48") (pintype "passive"))
      (node (ref "PIN_CONNECTIONS") (pin "16") (pinfunction "16_16") (pintype "passive"))
      (node (ref "SPECIAL_INSTRUMENT") (pin "1") (pinfunction "1_1") (pintype "passive"))
    )
    (net (code "120") (name "Net-(LO_TOM-Pad2)") (class "Default")
      (node (ref "LO_TOM") (pin "2") (pinfunction "2_2") (pintype "passive"))
      (node (ref "LO_TOM") (pin "4") (pinfunction "4_4") (pintype "passive"))
      (node (ref "MIXER") (pin "3") (pinfunction "3_3") (pintype "passive"))
    )
    (net (code "121") (name "Net-(MIXER-Pad4)") (class "Default")
      (node (ref "MIXER") (pin "4") (pinfunction "4_4") (pintype "passive"))
      (node (ref "SNARE_DRUM") (pin "2") (pinfunction "2_2") (pintype "passive"))
      (node (ref "SNARE_DRUM") (pin "4") (pinfunction "4_4") (pintype "passive"))
    )
    (net (code "122") (name "Net-(MIXER-Pad8)") (class "Default")
      (node (ref "MIXER") (pin "8") (pinfunction "8_8") (pintype "passive"))
      (node (ref "SPECIAL_INSTRUMENT") (pin "2") (pinfunction "2_2") (pintype "passive"))
      (node (ref "SPECIAL_INSTRUMENT") (pin "4") (pinfunction "4_4") (pintype "passive"))
    )
    (net (code "123") (name "Net-(PIN_CONNECTIONS-Pad1)") (class "Default")
      (node (ref "PIN_CONNECTIONS") (pin "1") (pinfunction "1_1") (pintype "passive"))
      (node (ref "SEQUENCER") (pin "2") (pinfunction "2_2") (pintype "passive"))
    )
    (net (code "124") (name "Net-(PIN_CONNECTIONS-Pad3)") (class "Default")
      (node (ref "PIN_CONNECTIONS") (pin "3") (pinfunction "3_3") (pintype "passive"))
      (node (ref "SEQUENCER") (pin "4") (pinfunction "4_4") (pintype "passive"))
    )
    (net (code "125") (name "Net-(PIN_CONNECTIONS-Pad5)") (class "Default")
      (node (ref "PIN_CONNECTIONS") (pin "5") (pinfunction "5_5") (pintype "passive"))
      (node (ref "SEQUENCER") (pin "6") (pinfunction "6_6") (pintype "passive"))
    )
    (net (code "126") (name "Net-(PIN_CONNECTIONS-Pad7)") (class "Default")
      (node (ref "PIN_CONNECTIONS") (pin "7") (pinfunction "7_7") (pintype "passive"))
      (node (ref "SEQUENCER") (pin "8") (pinfunction "8_8") (pintype "passive"))
    )
    (net (code "127") (name "Net-(PIN_CONNECTIONS-Pad9)") (class "Default")
      (node (ref "PIN_CONNECTIONS") (pin "9") (pinfunction "9_9") (pintype "passive"))
      (node (ref "SEQUENCER") (pin "10") (pinfunction "10_10") (pintype "passive"))
    )
    (net (code "128") (name "Net-(PIN_CONNECTIONS-Pad11)") (class "Default")
      (node (ref "PIN_CONNECTIONS") (pin "11") (pinfunction "11_11") (pintype "passive"))
      (node (ref "SEQUENCER") (pin "12") (pinfunction "12_12") (pintype "passive"))
    )
    (net (code "129") (name "Net-(PIN_CONNECTIONS-Pad13)") (class "Default")
      (node (ref "PIN_CONNECTIONS") (pin "13") (pinfunction "13_13") (pintype "passive"))
      (node (ref "SEQUENCER") (pin "14") (pinfunction "14_14") (pintype "passive"))
    )
    (net (code "130") (name "Net-(PIN_CONNECTIONS-Pad15)") (class "Default")
      (node (ref "PIN_CONNECTIONS") (pin "15") (pinfunction "15_15") (pintype "passive"))
      (node (ref "SEQUENCER") (pin "16") (pinfunction "16_16") (pintype "passive"))
    )
    (net (code "131") (name "OUTPUT") (class "Default")
      (node (ref "IC11") (pin "3") (pinfunction "O_3") (pintype "output"))
      (node (ref "IC15") (pin "3") (pinfunction "O_3") (pintype "output"))
      (node (ref "IC19") (pin "3") (pinfunction "O_3") (pintype "output"))
      (node (ref "IC23") (pin "3") (pinfunction "O_3") (pintype "output"))
      (node (ref "IC27") (pin "3") (pinfunction "O_3") (pintype "output"))
      (node (ref "IC3") (pin "3") (pinfunction "O_3") (pintype "output"))
      (node (ref "IC31") (pin "3") (pinfunction "O_3") (pintype "output"))
      (node (ref "IC35") (pin "3") (pinfunction "O_3") (pintype "output"))
      (node (ref "IC39") (pin "3") (pinfunction "O_3") (pintype "output"))
      (node (ref "IC43") (pin "3") (pinfunction "O_3") (pintype "output"))
      (node (ref "IC47") (pin "3") (pinfunction "O_3") (pintype "output"))
      (node (ref "IC51") (pin "3") (pinfunction "O_3") (pintype "output"))
      (node (ref "IC55") (pin "3") (pinfunction "O_3") (pintype "output"))
      (node (ref "IC59") (pin "3") (pinfunction "O_3") (pintype "output"))
      (node (ref "IC63") (pin "3") (pinfunction "O_3") (pintype "output"))
      (node (ref "IC7") (pin "3") (pinfunction "O_3") (pintype "output"))
    )
    (net (code "132") (name "VCC") (class "Default")
      (node (ref "C1") (pin "1") (pinfunction "1_1") (pintype "passive"))
      (node (ref "PIN_CONNECTIONS") (pin "17") (pinfunction "17_17") (pintype "passive"))
      (node (ref "POWER_SUPPY") (pin "1") (pinfunction "1_1") (pintype "passive"))
    )
    (net (code "133") (name "unconnected-(BUTTON_2-Pad1)") (class "Default")
      (node (ref "BUTTON_2") (pin "1") (pinfunction "1_1") (pintype "passive"))
    )
    (net (code "134") (name "unconnected-(BUTTON_3-Pad1)") (class "Default")
      (node (ref "BUTTON_3") (pin "1") (pinfunction "1_1") (pintype "passive"))
    )
    (net (code "135") (name "unconnected-(BUTTON_4-Pad1)") (class "Default")
      (node (ref "BUTTON_4") (pin "1") (pinfunction "1_1") (pintype "passive"))
    )
    (net (code "136") (name "unconnected-(BUTTON_5-Pad1)") (class "Default")
      (node (ref "BUTTON_5") (pin "1") (pinfunction "1_1") (pintype "passive"))
    )
    (net (code "137") (name "unconnected-(BUTTON_6-Pad1)") (class "Default")
      (node (ref "BUTTON_6") (pin "1") (pinfunction "1_1") (pintype "passive"))
    )
    (net (code "138") (name "unconnected-(BUTTON_7-Pad1)") (class "Default")
      (node (ref "BUTTON_7") (pin "1") (pinfunction "1_1") (pintype "passive"))
    )
    (net (code "139") (name "unconnected-(BUTTON_8-Pad1)") (class "Default")
      (node (ref "BUTTON_8") (pin "1") (pinfunction "1_1") (pintype "passive"))
    )
    (net (code "140") (name "unconnected-(BUTTON_9-Pad1)") (class "Default")
      (node (ref "BUTTON_9") (pin "1") (pinfunction "1_1") (pintype "passive"))
    )
    (net (code "141") (name "unconnected-(BUTTON_10-Pad1)") (class "Default")
      (node (ref "BUTTON_10") (pin "1") (pinfunction "1_1") (pintype "passive"))
    )
    (net (code "142") (name "unconnected-(BUTTON_11-Pad1)") (class "Default")
      (node (ref "BUTTON_11") (pin "1") (pinfunction "1_1") (pintype "passive"))
    )
    (net (code "143") (name "unconnected-(BUTTON_12-Pad1)") (class "Default")
      (node (ref "BUTTON_12") (pin "1") (pinfunction "1_1") (pintype "passive"))
    )
    (net (code "144") (name "unconnected-(BUTTON_13-Pad1)") (class "Default")
      (node (ref "BUTTON_13") (pin "1") (pinfunction "1_1") (pintype "passive"))
    )
    (net (code "145") (name "unconnected-(BUTTON_14-Pad1)") (class "Default")
      (node (ref "BUTTON_14") (pin "1") (pinfunction "1_1") (pintype "passive"))
    )
    (net (code "146") (name "unconnected-(BUTTON_15-Pad1)") (class "Default")
      (node (ref "BUTTON_15") (pin "1") (pinfunction "1_1") (pintype "passive"))
    )
    (net (code "147") (name "unconnected-(BUTTON_16-Pad1)") (class "Default")
      (node (ref "BUTTON_16") (pin "1") (pinfunction "1_1") (pintype "passive"))
    )
    (net (code "148") (name "unconnected-(KNOB_CONNECTIONS-Pad50)") (class "Default")
      (node (ref "KNOB_CONNECTIONS") (pin "50") (pinfunction "50_50") (pintype "passive"))
    )
    (net (code "149") (name "unconnected-(PIN_CONNECTIONS-Pad18)") (class "Default")
      (node (ref "PIN_CONNECTIONS") (pin "18") (pinfunction "18_18") (pintype "passive"))
    )
    (net (code "150") (name "unconnected-(SEQUENCER-Pad18)") (class "Default")
      (node (ref "SEQUENCER") (pin "18") (pinfunction "18_18") (pintype "passive"))
    )
  )
)
